# iv17-display-shield.net
KiCad netlist of a schematic drawn in EAGLE
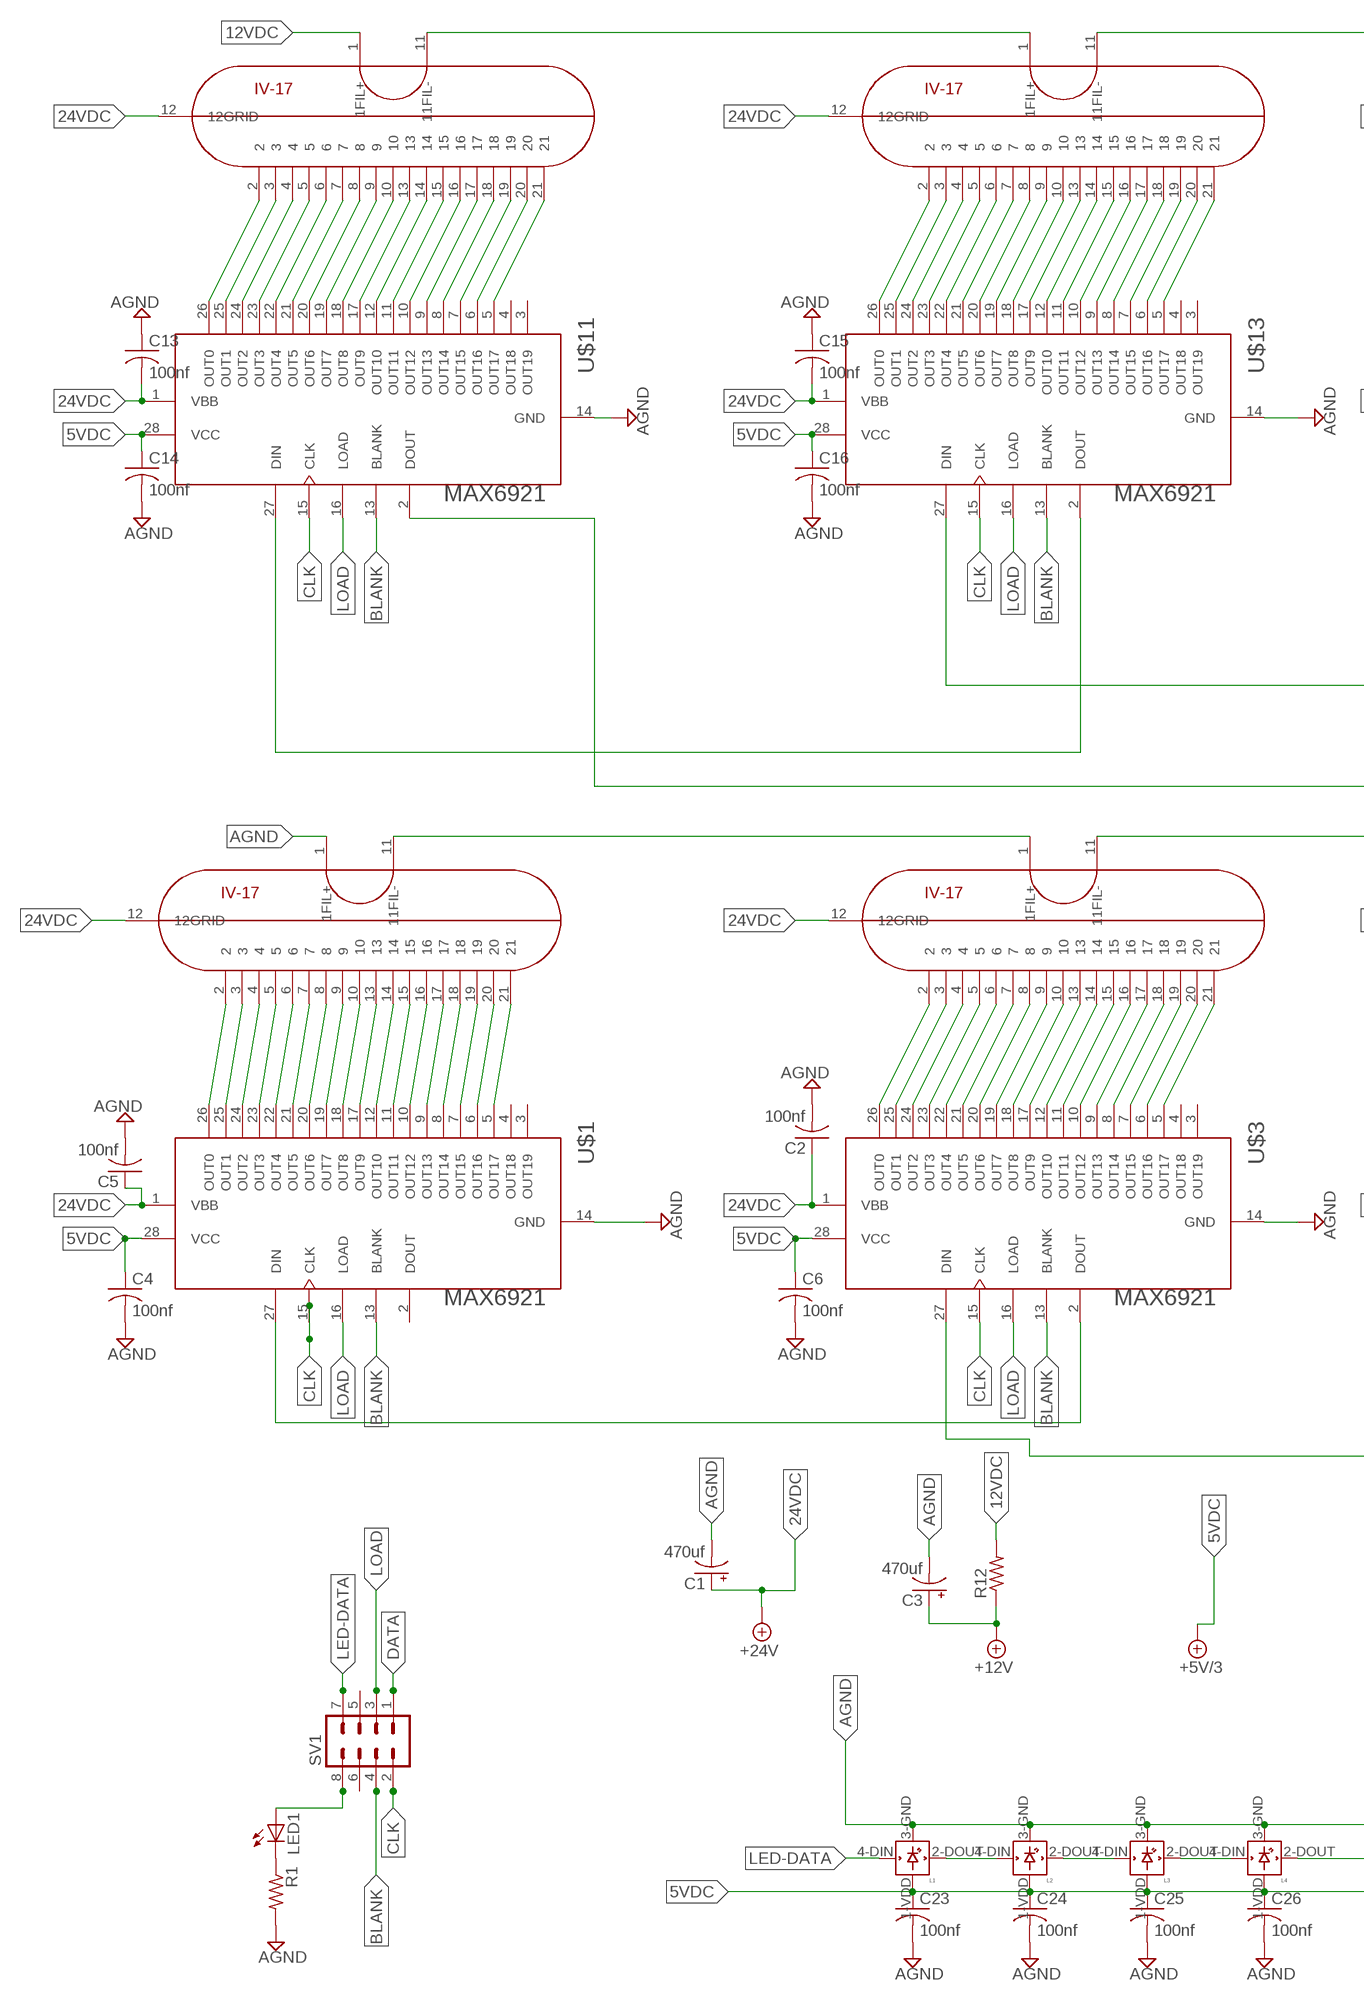
[diagram p0: schematic, sheet 1, part 1 of 2]
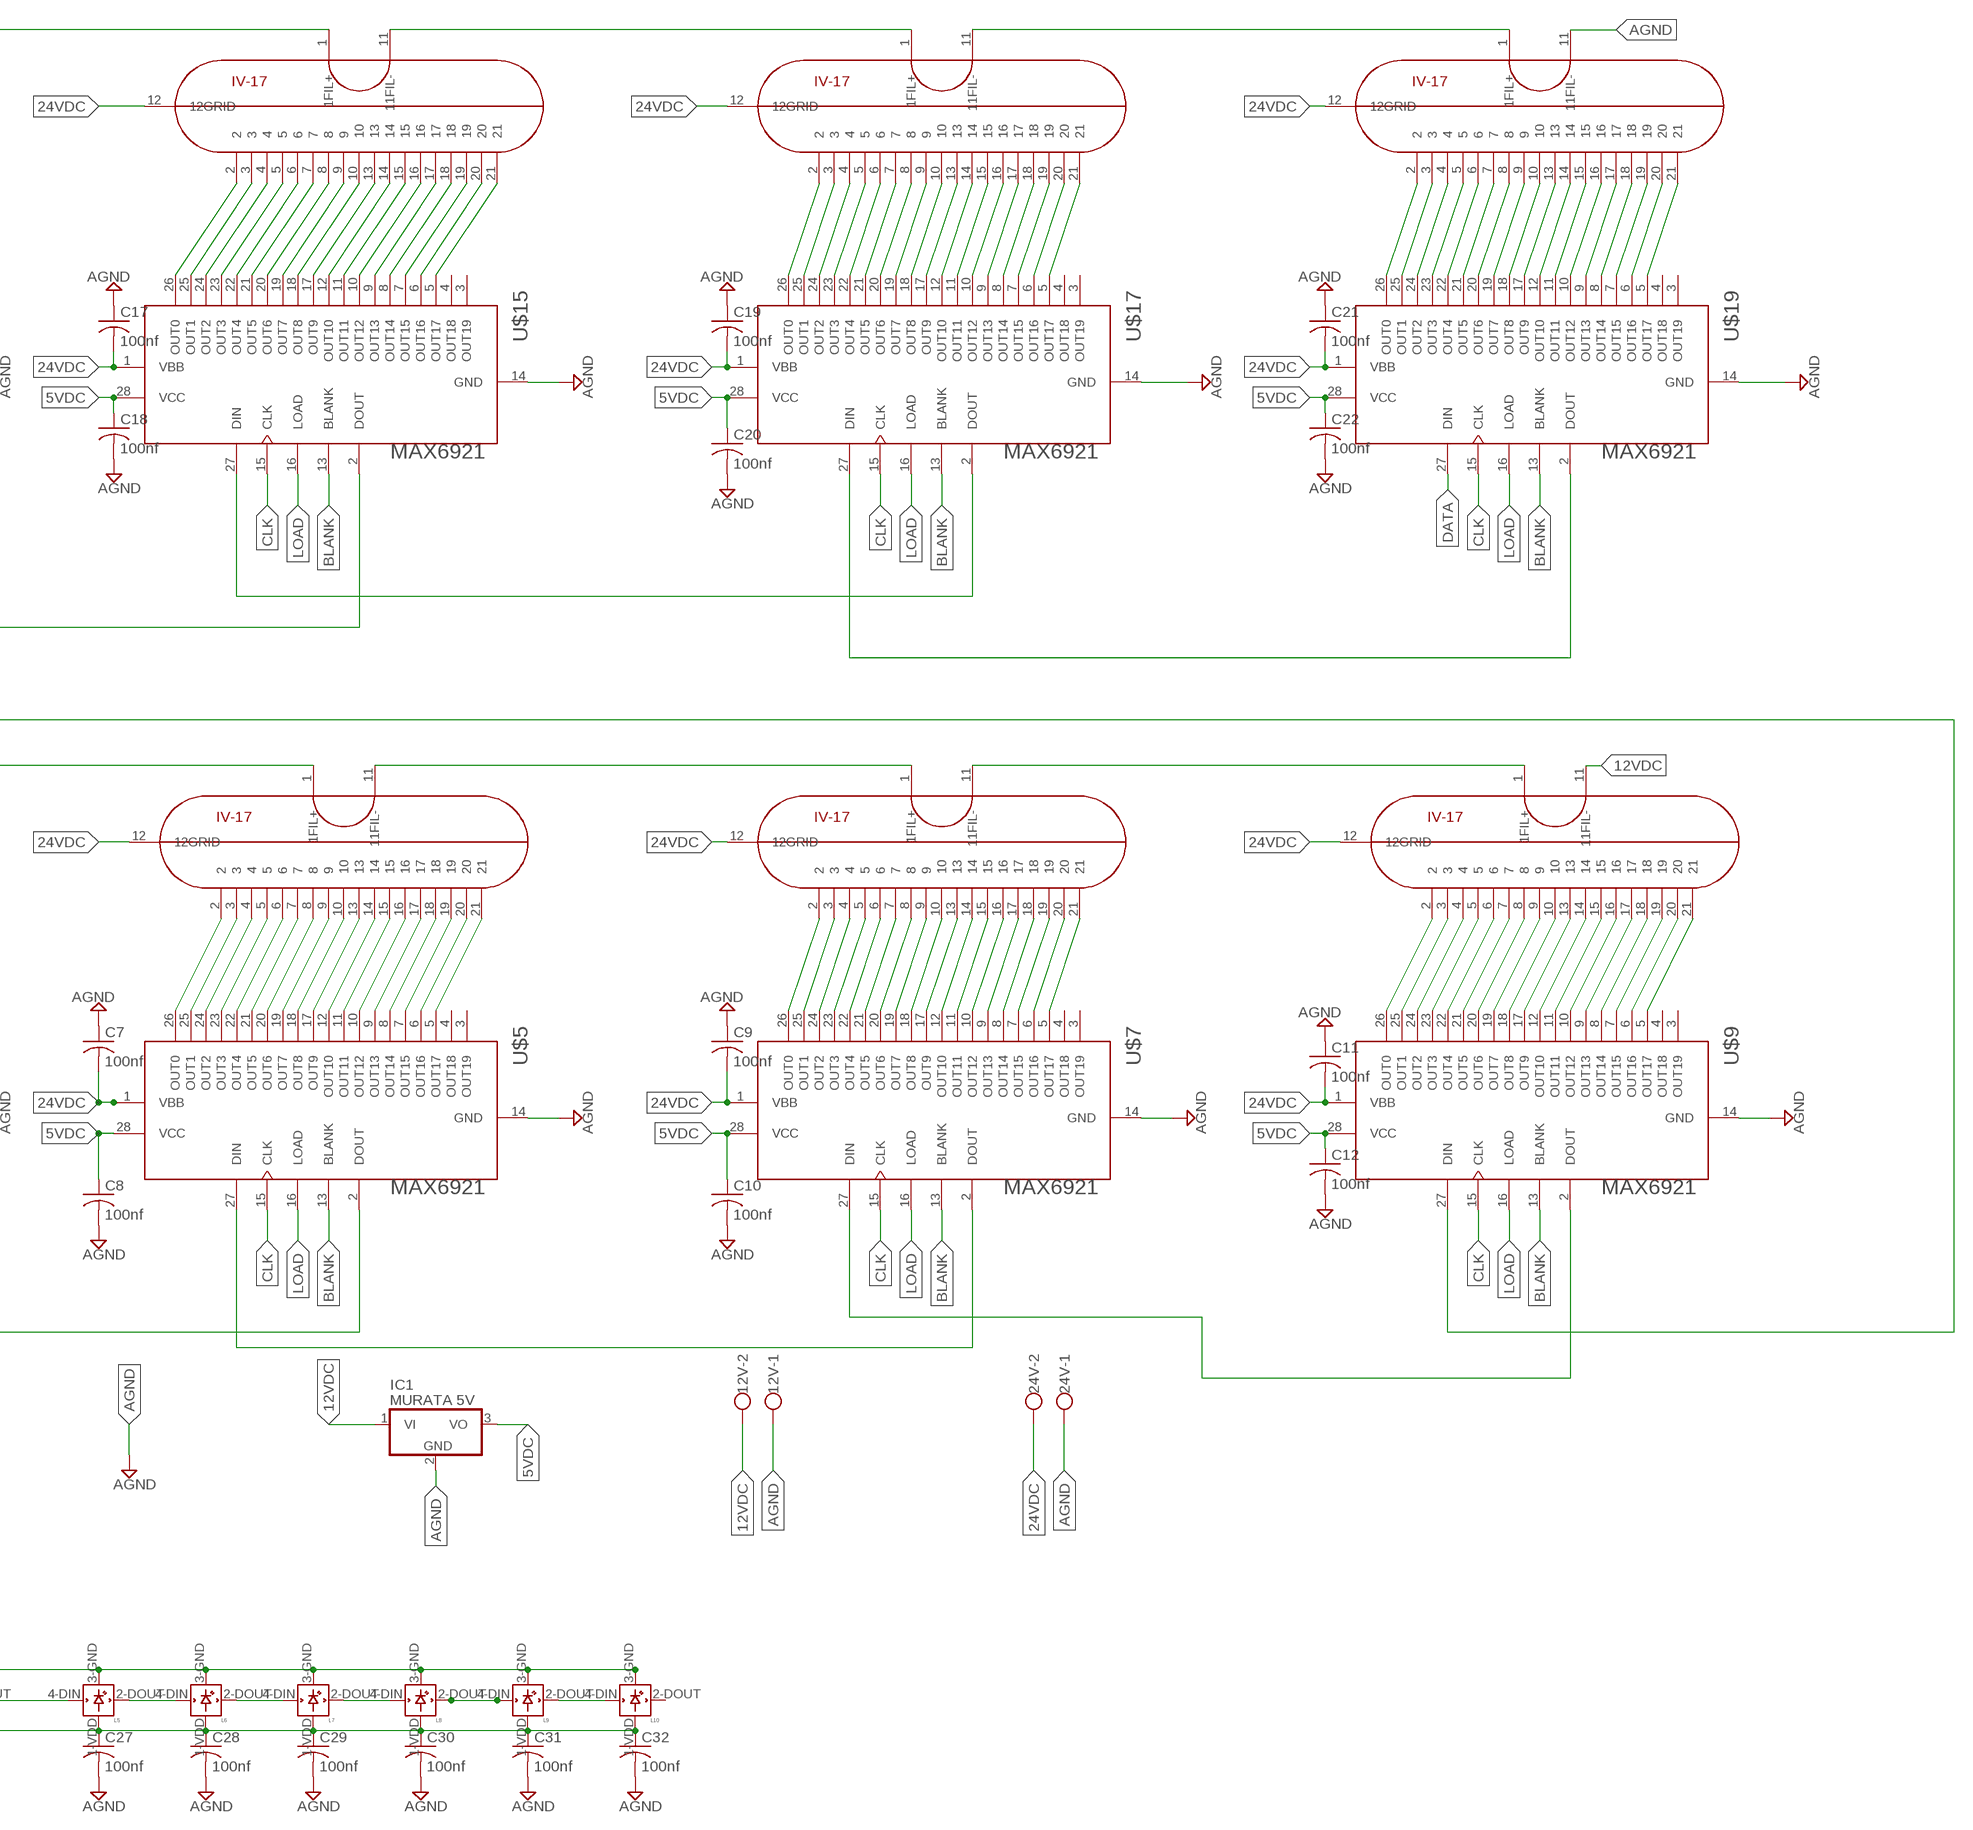
[diagram p1: schematic, sheet 1, part 2 of 2]

(export (version "E")
  (design (tool "Eeschema 10.0.6"))
  (components
    (comp (ref "12V")
      (value "W237-102")
      (footprint "eagle-import:W237-102")
      (fields (field (name "MPN") "237-102"))
      (libsource (lib "eagle-import") (part "W237-102"))
    )
    (comp (ref "24V")
      (value "W237-102")
      (footprint "eagle-import:W237-102")
      (fields (field (name "MPN") "237-102"))
      (libsource (lib "eagle-import") (part "W237-102"))
    )
    (comp (ref "C1")
      (value "470uf")
      (footprint "eagle-import:E5-10,5")
      (libsource (lib "eagle-import") (part "CPOL-USE5-10.5"))
    )
    (comp (ref "C2")
      (value "100nf")
      (footprint "eagle-import:C1206")
      (libsource (lib "eagle-import") (part "C-USC1206"))
    )
    (comp (ref "C3")
      (value "470uf")
      (footprint "eagle-import:E5-10,5")
      (libsource (lib "eagle-import") (part "CPOL-USE5-10.5"))
    )
    (comp (ref "C4")
      (value "100nf")
      (footprint "eagle-import:C1206")
      (libsource (lib "eagle-import") (part "C-USC1206"))
    )
    (comp (ref "C5")
      (value "100nf")
      (footprint "eagle-import:C1206")
      (libsource (lib "eagle-import") (part "C-USC1206"))
    )
    (comp (ref "C6")
      (value "100nf")
      (footprint "eagle-import:C1206")
      (libsource (lib "eagle-import") (part "C-USC1206"))
    )
    (comp (ref "C7")
      (value "100nf")
      (footprint "eagle-import:C1206")
      (libsource (lib "eagle-import") (part "C-USC1206"))
    )
    (comp (ref "C8")
      (value "100nf")
      (footprint "eagle-import:C1206")
      (libsource (lib "eagle-import") (part "C-USC1206"))
    )
    (comp (ref "C9")
      (value "100nf")
      (footprint "eagle-import:C1206")
      (libsource (lib "eagle-import") (part "C-USC1206"))
    )
    (comp (ref "C10")
      (value "100nf")
      (footprint "eagle-import:C1206")
      (libsource (lib "eagle-import") (part "C-USC1206"))
    )
    (comp (ref "C11")
      (value "100nf")
      (footprint "eagle-import:C1206")
      (libsource (lib "eagle-import") (part "C-USC1206"))
    )
    (comp (ref "C12")
      (value "100nf")
      (footprint "eagle-import:C1206")
      (libsource (lib "eagle-import") (part "C-USC1206"))
    )
    (comp (ref "C13")
      (value "100nf")
      (footprint "eagle-import:C1206")
      (libsource (lib "eagle-import") (part "C-USC1206"))
    )
    (comp (ref "C14")
      (value "100nf")
      (footprint "eagle-import:C1206")
      (libsource (lib "eagle-import") (part "C-USC1206"))
    )
    (comp (ref "C15")
      (value "100nf")
      (footprint "eagle-import:C1206")
      (libsource (lib "eagle-import") (part "C-USC1206"))
    )
    (comp (ref "C16")
      (value "100nf")
      (footprint "eagle-import:C1206")
      (libsource (lib "eagle-import") (part "C-USC1206"))
    )
    (comp (ref "C17")
      (value "100nf")
      (footprint "eagle-import:C1206")
      (libsource (lib "eagle-import") (part "C-USC1206"))
    )
    (comp (ref "C18")
      (value "100nf")
      (footprint "eagle-import:C1206")
      (libsource (lib "eagle-import") (part "C-USC1206"))
    )
    (comp (ref "C19")
      (value "100nf")
      (footprint "eagle-import:C1206")
      (libsource (lib "eagle-import") (part "C-USC1206"))
    )
    (comp (ref "C20")
      (value "100nf")
      (footprint "eagle-import:C1206")
      (libsource (lib "eagle-import") (part "C-USC1206"))
    )
    (comp (ref "C21")
      (value "100nf")
      (footprint "eagle-import:C1206")
      (libsource (lib "eagle-import") (part "C-USC1206"))
    )
    (comp (ref "C22")
      (value "100nf")
      (footprint "eagle-import:C1206")
      (libsource (lib "eagle-import") (part "C-USC1206"))
    )
    (comp (ref "C23")
      (value "100nf")
      (footprint "eagle-import:C1206")
      (libsource (lib "eagle-import") (part "C-USC1206"))
    )
    (comp (ref "C24")
      (value "100nf")
      (footprint "eagle-import:C1206")
      (libsource (lib "eagle-import") (part "C-USC1206"))
    )
    (comp (ref "C25")
      (value "100nf")
      (footprint "eagle-import:C1206")
      (libsource (lib "eagle-import") (part "C-USC1206"))
    )
    (comp (ref "C26")
      (value "100nf")
      (footprint "eagle-import:C1206")
      (libsource (lib "eagle-import") (part "C-USC1206"))
    )
    (comp (ref "C27")
      (value "100nf")
      (footprint "eagle-import:C1206")
      (libsource (lib "eagle-import") (part "C-USC1206"))
    )
    (comp (ref "C28")
      (value "100nf")
      (footprint "eagle-import:C1206")
      (libsource (lib "eagle-import") (part "C-USC1206"))
    )
    (comp (ref "C29")
      (value "100nf")
      (footprint "eagle-import:C1206")
      (libsource (lib "eagle-import") (part "C-USC1206"))
    )
    (comp (ref "C30")
      (value "100nf")
      (footprint "eagle-import:C1206")
      (libsource (lib "eagle-import") (part "C-USC1206"))
    )
    (comp (ref "C31")
      (value "100nf")
      (footprint "eagle-import:C1206")
      (libsource (lib "eagle-import") (part "C-USC1206"))
    )
    (comp (ref "C32")
      (value "100nf")
      (footprint "eagle-import:C1206")
      (libsource (lib "eagle-import") (part "C-USC1206"))
    )
    (comp (ref "IC1")
      (value "MURATA 5V")
      (footprint "eagle-import:TO220V")
      (libsource (lib "eagle-import") (part "78TV6"))
    )
    (comp (ref "L1")
      (value "WS2812B")
      (footprint "eagle-import:WS2812B")
      (libsource (lib "eagle-import") (part "WS2812B"))
    )
    (comp (ref "L2")
      (value "WS2812B")
      (footprint "eagle-import:WS2812B")
      (libsource (lib "eagle-import") (part "WS2812B"))
    )
    (comp (ref "L3")
      (value "WS2812B")
      (footprint "eagle-import:WS2812B")
      (libsource (lib "eagle-import") (part "WS2812B"))
    )
    (comp (ref "L4")
      (value "WS2812B")
      (footprint "eagle-import:WS2812B")
      (libsource (lib "eagle-import") (part "WS2812B"))
    )
    (comp (ref "L5")
      (value "WS2812B")
      (footprint "eagle-import:WS2812B")
      (libsource (lib "eagle-import") (part "WS2812B"))
    )
    (comp (ref "L6")
      (value "WS2812B")
      (footprint "eagle-import:WS2812B")
      (libsource (lib "eagle-import") (part "WS2812B"))
    )
    (comp (ref "L7")
      (value "WS2812B")
      (footprint "eagle-import:WS2812B")
      (libsource (lib "eagle-import") (part "WS2812B"))
    )
    (comp (ref "L8")
      (value "WS2812B")
      (footprint "eagle-import:WS2812B")
      (libsource (lib "eagle-import") (part "WS2812B"))
    )
    (comp (ref "L9")
      (value "WS2812B")
      (footprint "eagle-import:WS2812B")
      (libsource (lib "eagle-import") (part "WS2812B"))
    )
    (comp (ref "L10")
      (value "WS2812B")
      (footprint "eagle-import:WS2812B")
      (libsource (lib "eagle-import") (part "WS2812B"))
    )
    (comp (ref "LED1")
      (value "LEDSMT1206")
      (footprint "eagle-import:1206")
      (libsource (lib "eagle-import") (part "LEDSMT1206"))
    )
    (comp (ref "R1")
      (value "R-US_R1206")
      (footprint "eagle-import:R1206")
      (libsource (lib "eagle-import") (part "R-US_R1206"))
    )
    (comp (ref "R12")
      (value "R-US_0207/10")
      (footprint "eagle-import:0207_10")
      (libsource (lib "eagle-import") (part "R-US_0207/10"))
    )
    (comp (ref "SV1")
      (value "MA04-2")
      (footprint "eagle-import:MA04-2")
      (libsource (lib "eagle-import") (part "MA04-2"))
    )
    (comp (ref "U$1")
      (value "MAX6921")
      (footprint "eagle-import:SOIC-28W")
      (libsource (lib "eagle-import") (part "MAX6921"))
    )
    (comp (ref "U$2")
      (value "IV17")
      (footprint "eagle-import:NIXIE-22")
      (libsource (lib "eagle-import") (part "IV17"))
    )
    (comp (ref "U$3")
      (value "MAX6921")
      (footprint "eagle-import:SOIC-28W")
      (libsource (lib "eagle-import") (part "MAX6921"))
    )
    (comp (ref "U$4")
      (value "IV17")
      (footprint "eagle-import:NIXIE-22")
      (libsource (lib "eagle-import") (part "IV17"))
    )
    (comp (ref "U$5")
      (value "MAX6921")
      (footprint "eagle-import:SOIC-28W")
      (libsource (lib "eagle-import") (part "MAX6921"))
    )
    (comp (ref "U$6")
      (value "IV17")
      (footprint "eagle-import:NIXIE-22")
      (libsource (lib "eagle-import") (part "IV17"))
    )
    (comp (ref "U$7")
      (value "MAX6921")
      (footprint "eagle-import:SOIC-28W")
      (libsource (lib "eagle-import") (part "MAX6921"))
    )
    (comp (ref "U$8")
      (value "IV17")
      (footprint "eagle-import:NIXIE-22")
      (libsource (lib "eagle-import") (part "IV17"))
    )
    (comp (ref "U$9")
      (value "MAX6921")
      (footprint "eagle-import:SOIC-28W")
      (libsource (lib "eagle-import") (part "MAX6921"))
    )
    (comp (ref "U$10")
      (value "IV17")
      (footprint "eagle-import:NIXIE-22")
      (libsource (lib "eagle-import") (part "IV17"))
    )
    (comp (ref "U$11")
      (value "MAX6921")
      (footprint "eagle-import:SOIC-28W")
      (libsource (lib "eagle-import") (part "MAX6921"))
    )
    (comp (ref "U$12")
      (value "IV17")
      (footprint "eagle-import:NIXIE-22")
      (libsource (lib "eagle-import") (part "IV17"))
    )
    (comp (ref "U$13")
      (value "MAX6921")
      (footprint "eagle-import:SOIC-28W")
      (libsource (lib "eagle-import") (part "MAX6921"))
    )
    (comp (ref "U$14")
      (value "IV17")
      (footprint "eagle-import:NIXIE-22")
      (libsource (lib "eagle-import") (part "IV17"))
    )
    (comp (ref "U$15")
      (value "MAX6921")
      (footprint "eagle-import:SOIC-28W")
      (libsource (lib "eagle-import") (part "MAX6921"))
    )
    (comp (ref "U$16")
      (value "IV17")
      (footprint "eagle-import:NIXIE-22")
      (libsource (lib "eagle-import") (part "IV17"))
    )
    (comp (ref "U$17")
      (value "MAX6921")
      (footprint "eagle-import:SOIC-28W")
      (libsource (lib "eagle-import") (part "MAX6921"))
    )
    (comp (ref "U$18")
      (value "IV17")
      (footprint "eagle-import:NIXIE-22")
      (libsource (lib "eagle-import") (part "IV17"))
    )
    (comp (ref "U$19")
      (value "MAX6921")
      (footprint "eagle-import:SOIC-28W")
      (libsource (lib "eagle-import") (part "MAX6921"))
    )
    (comp (ref "U$20")
      (value "IV17")
      (footprint "eagle-import:NIXIE-22")
      (libsource (lib "eagle-import") (part "IV17"))
    )
  )
  (nets
    (net (code "1") (name "+12V") (class "Default")
      (node (ref "C3") (pin "+") (pinfunction "+_+") (pintype "passive"))
      (node (ref "R12") (pin "1") (pinfunction "1_1") (pintype "passive"))
    )
    (net (code "2") (name "5VDC") (class "Default")
      (node (ref "C10") (pin "1") (pinfunction "1_1") (pintype "passive"))
      (node (ref "C12") (pin "1") (pinfunction "1_1") (pintype "passive"))
      (node (ref "C14") (pin "1") (pinfunction "1_1") (pintype "passive"))
      (node (ref "C16") (pin "1") (pinfunction "1_1") (pintype "passive"))
      (node (ref "C18") (pin "1") (pinfunction "1_1") (pintype "passive"))
      (node (ref "C20") (pin "1") (pinfunction "1_1") (pintype "passive"))
      (node (ref "C22") (pin "1") (pinfunction "1_1") (pintype "passive"))
      (node (ref "C23") (pin "1") (pinfunction "1_1") (pintype "passive"))
      (node (ref "C24") (pin "1") (pinfunction "1_1") (pintype "passive"))
      (node (ref "C25") (pin "1") (pinfunction "1_1") (pintype "passive"))
      (node (ref "C26") (pin "1") (pinfunction "1_1") (pintype "passive"))
      (node (ref "C27") (pin "1") (pinfunction "1_1") (pintype "passive"))
      (node (ref "C28") (pin "1") (pinfunction "1_1") (pintype "passive"))
      (node (ref "C29") (pin "1") (pinfunction "1_1") (pintype "passive"))
      (node (ref "C30") (pin "1") (pinfunction "1_1") (pintype "passive"))
      (node (ref "C31") (pin "1") (pinfunction "1_1") (pintype "passive"))
      (node (ref "C32") (pin "1") (pinfunction "1_1") (pintype "passive"))
      (node (ref "C4") (pin "1") (pinfunction "1_1") (pintype "passive"))
      (node (ref "C6") (pin "1") (pinfunction "1_1") (pintype "passive"))
      (node (ref "C8") (pin "1") (pinfunction "1_1") (pintype "passive"))
      (node (ref "IC1") (pin "3") (pinfunction "VO_3") (pintype "passive"))
      (node (ref "L1") (pin "1-VDD") (pinfunction "VDD_1-VDD") (pintype "bidirectional"))
      (node (ref "L10") (pin "1-VDD") (pinfunction "VDD_1-VDD") (pintype "bidirectional"))
      (node (ref "L2") (pin "1-VDD") (pinfunction "VDD_1-VDD") (pintype "bidirectional"))
      (node (ref "L3") (pin "1-VDD") (pinfunction "VDD_1-VDD") (pintype "bidirectional"))
      (node (ref "L4") (pin "1-VDD") (pinfunction "VDD_1-VDD") (pintype "bidirectional"))
      (node (ref "L5") (pin "1-VDD") (pinfunction "VDD_1-VDD") (pintype "bidirectional"))
      (node (ref "L6") (pin "1-VDD") (pinfunction "VDD_1-VDD") (pintype "bidirectional"))
      (node (ref "L7") (pin "1-VDD") (pinfunction "VDD_1-VDD") (pintype "bidirectional"))
      (node (ref "L8") (pin "1-VDD") (pinfunction "VDD_1-VDD") (pintype "bidirectional"))
      (node (ref "L9") (pin "1-VDD") (pinfunction "VDD_1-VDD") (pintype "bidirectional"))
      (node (ref "U$1") (pin "28") (pinfunction "VCC_28") (pintype "power_in"))
      (node (ref "U$11") (pin "28") (pinfunction "VCC_28") (pintype "power_in"))
      (node (ref "U$13") (pin "28") (pinfunction "VCC_28") (pintype "power_in"))
      (node (ref "U$15") (pin "28") (pinfunction "VCC_28") (pintype "power_in"))
      (node (ref "U$17") (pin "28") (pinfunction "VCC_28") (pintype "power_in"))
      (node (ref "U$19") (pin "28") (pinfunction "VCC_28") (pintype "power_in"))
      (node (ref "U$3") (pin "28") (pinfunction "VCC_28") (pintype "power_in"))
      (node (ref "U$5") (pin "28") (pinfunction "VCC_28") (pintype "power_in"))
      (node (ref "U$7") (pin "28") (pinfunction "VCC_28") (pintype "power_in"))
      (node (ref "U$9") (pin "28") (pinfunction "VCC_28") (pintype "power_in"))
    )
    (net (code "3") (name "12VDC") (class "Default")
      (node (ref "12V") (pin "2") (pinfunction "KL_2") (pintype "passive"))
      (node (ref "IC1") (pin "1") (pinfunction "VI_1") (pintype "input"))
      (node (ref "R12") (pin "2") (pinfunction "2_2") (pintype "passive"))
      (node (ref "U$10") (pin "11") (pinfunction "11FIL-_11") (pintype "bidirectional"))
      (node (ref "U$12") (pin "1") (pinfunction "1FIL+_1") (pintype "bidirectional"))
    )
    (net (code "4") (name "24VDC") (class "Default")
      (node (ref "24V") (pin "2") (pinfunction "KL_2") (pintype "passive"))
      (node (ref "C1") (pin "+") (pinfunction "+_+") (pintype "passive"))
      (node (ref "C11") (pin "2") (pinfunction "2_2") (pintype "passive"))
      (node (ref "C13") (pin "2") (pinfunction "2_2") (pintype "passive"))
      (node (ref "C15") (pin "2") (pinfunction "2_2") (pintype "passive"))
      (node (ref "C17") (pin "2") (pinfunction "2_2") (pintype "passive"))
      (node (ref "C19") (pin "2") (pinfunction "2_2") (pintype "passive"))
      (node (ref "C2") (pin "1") (pinfunction "1_1") (pintype "passive"))
      (node (ref "C21") (pin "2") (pinfunction "2_2") (pintype "passive"))
      (node (ref "C5") (pin "1") (pinfunction "1_1") (pintype "passive"))
      (node (ref "C7") (pin "2") (pinfunction "2_2") (pintype "passive"))
      (node (ref "C9") (pin "2") (pinfunction "2_2") (pintype "passive"))
      (node (ref "U$1") (pin "1") (pinfunction "VBB_1") (pintype "power_in"))
      (node (ref "U$10") (pin "12") (pinfunction "12GRID_12") (pintype "bidirectional"))
      (node (ref "U$11") (pin "1") (pinfunction "VBB_1") (pintype "power_in"))
      (node (ref "U$12") (pin "12") (pinfunction "12GRID_12") (pintype "bidirectional"))
      (node (ref "U$13") (pin "1") (pinfunction "VBB_1") (pintype "power_in"))
      (node (ref "U$14") (pin "12") (pinfunction "12GRID_12") (pintype "bidirectional"))
      (node (ref "U$15") (pin "1") (pinfunction "VBB_1") (pintype "power_in"))
      (node (ref "U$16") (pin "12") (pinfunction "12GRID_12") (pintype "bidirectional"))
      (node (ref "U$17") (pin "1") (pinfunction "VBB_1") (pintype "power_in"))
      (node (ref "U$18") (pin "12") (pinfunction "12GRID_12") (pintype "bidirectional"))
      (node (ref "U$19") (pin "1") (pinfunction "VBB_1") (pintype "power_in"))
      (node (ref "U$2") (pin "12") (pinfunction "12GRID_12") (pintype "bidirectional"))
      (node (ref "U$20") (pin "12") (pinfunction "12GRID_12") (pintype "bidirectional"))
      (node (ref "U$3") (pin "1") (pinfunction "VBB_1") (pintype "power_in"))
      (node (ref "U$4") (pin "12") (pinfunction "12GRID_12") (pintype "bidirectional"))
      (node (ref "U$5") (pin "1") (pinfunction "VBB_1") (pintype "power_in"))
      (node (ref "U$6") (pin "12") (pinfunction "12GRID_12") (pintype "bidirectional"))
      (node (ref "U$7") (pin "1") (pinfunction "VBB_1") (pintype "power_in"))
      (node (ref "U$8") (pin "12") (pinfunction "12GRID_12") (pintype "bidirectional"))
      (node (ref "U$9") (pin "1") (pinfunction "VBB_1") (pintype "power_in"))
    )
    (net (code "5") (name "AGND") (class "Default")
      (node (ref "12V") (pin "1") (pinfunction "KL_1") (pintype "passive"))
      (node (ref "24V") (pin "1") (pinfunction "KL_1") (pintype "passive"))
      (node (ref "C1") (pin "-") (pinfunction "-_-") (pintype "passive"))
      (node (ref "C10") (pin "2") (pinfunction "2_2") (pintype "passive"))
      (node (ref "C11") (pin "1") (pinfunction "1_1") (pintype "passive"))
      (node (ref "C12") (pin "2") (pinfunction "2_2") (pintype "passive"))
      (node (ref "C13") (pin "1") (pinfunction "1_1") (pintype "passive"))
      (node (ref "C14") (pin "2") (pinfunction "2_2") (pintype "passive"))
      (node (ref "C15") (pin "1") (pinfunction "1_1") (pintype "passive"))
      (node (ref "C16") (pin "2") (pinfunction "2_2") (pintype "passive"))
      (node (ref "C17") (pin "1") (pinfunction "1_1") (pintype "passive"))
      (node (ref "C18") (pin "2") (pinfunction "2_2") (pintype "passive"))
      (node (ref "C19") (pin "1") (pinfunction "1_1") (pintype "passive"))
      (node (ref "C2") (pin "2") (pinfunction "2_2") (pintype "passive"))
      (node (ref "C20") (pin "2") (pinfunction "2_2") (pintype "passive"))
      (node (ref "C21") (pin "1") (pinfunction "1_1") (pintype "passive"))
      (node (ref "C22") (pin "2") (pinfunction "2_2") (pintype "passive"))
      (node (ref "C23") (pin "2") (pinfunction "2_2") (pintype "passive"))
      (node (ref "C24") (pin "2") (pinfunction "2_2") (pintype "passive"))
      (node (ref "C25") (pin "2") (pinfunction "2_2") (pintype "passive"))
      (node (ref "C26") (pin "2") (pinfunction "2_2") (pintype "passive"))
      (node (ref "C27") (pin "2") (pinfunction "2_2") (pintype "passive"))
      (node (ref "C28") (pin "2") (pinfunction "2_2") (pintype "passive"))
      (node (ref "C29") (pin "2") (pinfunction "2_2") (pintype "passive"))
      (node (ref "C3") (pin "-") (pinfunction "-_-") (pintype "passive"))
      (node (ref "C30") (pin "2") (pinfunction "2_2") (pintype "passive"))
      (node (ref "C31") (pin "2") (pinfunction "2_2") (pintype "passive"))
      (node (ref "C32") (pin "2") (pinfunction "2_2") (pintype "passive"))
      (node (ref "C4") (pin "2") (pinfunction "2_2") (pintype "passive"))
      (node (ref "C5") (pin "2") (pinfunction "2_2") (pintype "passive"))
      (node (ref "C6") (pin "2") (pinfunction "2_2") (pintype "passive"))
      (node (ref "C7") (pin "1") (pinfunction "1_1") (pintype "passive"))
      (node (ref "C8") (pin "2") (pinfunction "2_2") (pintype "passive"))
      (node (ref "C9") (pin "1") (pinfunction "1_1") (pintype "passive"))
      (node (ref "IC1") (pin "2") (pinfunction "GND_2") (pintype "passive"))
      (node (ref "L1") (pin "3-GND") (pinfunction "GND_3-GND") (pintype "bidirectional"))
      (node (ref "L10") (pin "3-GND") (pinfunction "GND_3-GND") (pintype "bidirectional"))
      (node (ref "L2") (pin "3-GND") (pinfunction "GND_3-GND") (pintype "bidirectional"))
      (node (ref "L3") (pin "3-GND") (pinfunction "GND_3-GND") (pintype "bidirectional"))
      (node (ref "L4") (pin "3-GND") (pinfunction "GND_3-GND") (pintype "bidirectional"))
      (node (ref "L5") (pin "3-GND") (pinfunction "GND_3-GND") (pintype "bidirectional"))
      (node (ref "L6") (pin "3-GND") (pinfunction "GND_3-GND") (pintype "bidirectional"))
      (node (ref "L7") (pin "3-GND") (pinfunction "GND_3-GND") (pintype "bidirectional"))
      (node (ref "L8") (pin "3-GND") (pinfunction "GND_3-GND") (pintype "bidirectional"))
      (node (ref "L9") (pin "3-GND") (pinfunction "GND_3-GND") (pintype "bidirectional"))
      (node (ref "R1") (pin "2") (pinfunction "2_2") (pintype "passive"))
      (node (ref "U$1") (pin "14") (pinfunction "GND_14") (pintype "power_in"))
      (node (ref "U$11") (pin "14") (pinfunction "GND_14") (pintype "power_in"))
      (node (ref "U$13") (pin "14") (pinfunction "GND_14") (pintype "power_in"))
      (node (ref "U$15") (pin "14") (pinfunction "GND_14") (pintype "power_in"))
      (node (ref "U$17") (pin "14") (pinfunction "GND_14") (pintype "power_in"))
      (node (ref "U$19") (pin "14") (pinfunction "GND_14") (pintype "power_in"))
      (node (ref "U$2") (pin "1") (pinfunction "1FIL+_1") (pintype "bidirectional"))
      (node (ref "U$20") (pin "11") (pinfunction "11FIL-_11") (pintype "bidirectional"))
      (node (ref "U$3") (pin "14") (pinfunction "GND_14") (pintype "power_in"))
      (node (ref "U$5") (pin "14") (pinfunction "GND_14") (pintype "power_in"))
      (node (ref "U$7") (pin "14") (pinfunction "GND_14") (pintype "power_in"))
      (node (ref "U$9") (pin "14") (pinfunction "GND_14") (pintype "power_in"))
    )
    (net (code "6") (name "BLANK") (class "Default")
      (node (ref "SV1") (pin "4") (pinfunction "4_4") (pintype "passive"))
      (node (ref "U$1") (pin "13") (pinfunction "BLANK_13") (pintype "input"))
      (node (ref "U$11") (pin "13") (pinfunction "BLANK_13") (pintype "input"))
      (node (ref "U$13") (pin "13") (pinfunction "BLANK_13") (pintype "input"))
      (node (ref "U$15") (pin "13") (pinfunction "BLANK_13") (pintype "input"))
      (node (ref "U$17") (pin "13") (pinfunction "BLANK_13") (pintype "input"))
      (node (ref "U$19") (pin "13") (pinfunction "BLANK_13") (pintype "input"))
      (node (ref "U$3") (pin "13") (pinfunction "BLANK_13") (pintype "input"))
      (node (ref "U$5") (pin "13") (pinfunction "BLANK_13") (pintype "input"))
      (node (ref "U$7") (pin "13") (pinfunction "BLANK_13") (pintype "input"))
      (node (ref "U$9") (pin "13") (pinfunction "BLANK_13") (pintype "input"))
    )
    (net (code "7") (name "CLK") (class "Default")
      (node (ref "SV1") (pin "2") (pinfunction "2_2") (pintype "passive"))
      (node (ref "U$1") (pin "15") (pinfunction "CLK_15") (pintype "input"))
      (node (ref "U$11") (pin "15") (pinfunction "CLK_15") (pintype "input"))
      (node (ref "U$13") (pin "15") (pinfunction "CLK_15") (pintype "input"))
      (node (ref "U$15") (pin "15") (pinfunction "CLK_15") (pintype "input"))
      (node (ref "U$17") (pin "15") (pinfunction "CLK_15") (pintype "input"))
      (node (ref "U$19") (pin "15") (pinfunction "CLK_15") (pintype "input"))
      (node (ref "U$3") (pin "15") (pinfunction "CLK_15") (pintype "input"))
      (node (ref "U$5") (pin "15") (pinfunction "CLK_15") (pintype "input"))
      (node (ref "U$7") (pin "15") (pinfunction "CLK_15") (pintype "input"))
      (node (ref "U$9") (pin "15") (pinfunction "CLK_15") (pintype "input"))
    )
    (net (code "8") (name "DATA") (class "Default")
      (node (ref "SV1") (pin "1") (pinfunction "1_1") (pintype "passive"))
      (node (ref "U$19") (pin "27") (pinfunction "DIN_27") (pintype "input"))
    )
    (net (code "9") (name "LED-DATA") (class "Default")
      (node (ref "L1") (pin "4-DIN") (pinfunction "DIN_4-DIN") (pintype "input"))
      (node (ref "SV1") (pin "7") (pinfunction "7_7") (pintype "passive"))
    )
    (net (code "10") (name "LOAD") (class "Default")
      (node (ref "SV1") (pin "3") (pinfunction "3_3") (pintype "passive"))
      (node (ref "U$1") (pin "16") (pinfunction "LOAD_16") (pintype "input"))
      (node (ref "U$11") (pin "16") (pinfunction "LOAD_16") (pintype "input"))
      (node (ref "U$13") (pin "16") (pinfunction "LOAD_16") (pintype "input"))
      (node (ref "U$15") (pin "16") (pinfunction "LOAD_16") (pintype "input"))
      (node (ref "U$17") (pin "16") (pinfunction "LOAD_16") (pintype "input"))
      (node (ref "U$19") (pin "16") (pinfunction "LOAD_16") (pintype "input"))
      (node (ref "U$3") (pin "16") (pinfunction "LOAD_16") (pintype "input"))
      (node (ref "U$5") (pin "16") (pinfunction "LOAD_16") (pintype "input"))
      (node (ref "U$7") (pin "16") (pinfunction "LOAD_16") (pintype "input"))
      (node (ref "U$9") (pin "16") (pinfunction "LOAD_16") (pintype "input"))
    )
    (net (code "11") (name "Net-(L1-DOUT)") (class "Default")
      (node (ref "L1") (pin "2-DOUT") (pinfunction "DOUT_2-DOUT") (pintype "output"))
      (node (ref "L2") (pin "4-DIN") (pinfunction "DIN_4-DIN") (pintype "input"))
    )
    (net (code "12") (name "Net-(L2-DOUT)") (class "Default")
      (node (ref "L2") (pin "2-DOUT") (pinfunction "DOUT_2-DOUT") (pintype "output"))
      (node (ref "L3") (pin "4-DIN") (pinfunction "DIN_4-DIN") (pintype "input"))
    )
    (net (code "13") (name "Net-(L3-DOUT)") (class "Default")
      (node (ref "L3") (pin "2-DOUT") (pinfunction "DOUT_2-DOUT") (pintype "output"))
      (node (ref "L4") (pin "4-DIN") (pinfunction "DIN_4-DIN") (pintype "input"))
    )
    (net (code "14") (name "Net-(L4-DOUT)") (class "Default")
      (node (ref "L4") (pin "2-DOUT") (pinfunction "DOUT_2-DOUT") (pintype "output"))
      (node (ref "L5") (pin "4-DIN") (pinfunction "DIN_4-DIN") (pintype "input"))
    )
    (net (code "15") (name "Net-(L5-DOUT)") (class "Default")
      (node (ref "L5") (pin "2-DOUT") (pinfunction "DOUT_2-DOUT") (pintype "output"))
      (node (ref "L6") (pin "4-DIN") (pinfunction "DIN_4-DIN") (pintype "input"))
    )
    (net (code "16") (name "Net-(L6-DOUT)") (class "Default")
      (node (ref "L6") (pin "2-DOUT") (pinfunction "DOUT_2-DOUT") (pintype "output"))
      (node (ref "L7") (pin "4-DIN") (pinfunction "DIN_4-DIN") (pintype "input"))
    )
    (net (code "17") (name "Net-(L7-DOUT)") (class "Default")
      (node (ref "L7") (pin "2-DOUT") (pinfunction "DOUT_2-DOUT") (pintype "output"))
      (node (ref "L8") (pin "4-DIN") (pinfunction "DIN_4-DIN") (pintype "input"))
    )
    (net (code "18") (name "Net-(L8-DOUT)") (class "Default")
      (node (ref "L8") (pin "2-DOUT") (pinfunction "DOUT_2-DOUT") (pintype "output"))
      (node (ref "L9") (pin "4-DIN") (pinfunction "DIN_4-DIN") (pintype "input"))
    )
    (net (code "19") (name "Net-(L10-DIN)") (class "Default")
      (node (ref "L10") (pin "4-DIN") (pinfunction "DIN_4-DIN") (pintype "input"))
      (node (ref "L9") (pin "2-DOUT") (pinfunction "DOUT_2-DOUT") (pintype "output"))
    )
    (net (code "20") (name "Net-(LED1-PadA)") (class "Default")
      (node (ref "LED1") (pin "A") (pinfunction "A_A") (pintype "passive"))
      (node (ref "SV1") (pin "8") (pinfunction "8_8") (pintype "passive"))
    )
    (net (code "21") (name "Net-(LED1-PadC)") (class "Default")
      (node (ref "LED1") (pin "C") (pinfunction "C_C") (pintype "passive"))
      (node (ref "R1") (pin "1") (pinfunction "1_1") (pintype "passive"))
    )
    (net (code "22") (name "Net-(U$1-DIN)") (class "Default")
      (node (ref "U$1") (pin "27") (pinfunction "DIN_27") (pintype "input"))
      (node (ref "U$3") (pin "2") (pinfunction "DOUT_2") (pintype "output"))
    )
    (net (code "23") (name "Net-(U$1-OUT0)") (class "Default")
      (node (ref "U$1") (pin "26") (pinfunction "OUT0_26") (pintype "output"))
      (node (ref "U$2") (pin "2") (pinfunction "2_2") (pintype "bidirectional"))
    )
    (net (code "24") (name "Net-(U$1-OUT1)") (class "Default")
      (node (ref "U$1") (pin "25") (pinfunction "OUT1_25") (pintype "output"))
      (node (ref "U$2") (pin "3") (pinfunction "3_3") (pintype "bidirectional"))
    )
    (net (code "25") (name "Net-(U$1-OUT2)") (class "Default")
      (node (ref "U$1") (pin "24") (pinfunction "OUT2_24") (pintype "output"))
      (node (ref "U$2") (pin "4") (pinfunction "4_4") (pintype "bidirectional"))
    )
    (net (code "26") (name "Net-(U$1-OUT3)") (class "Default")
      (node (ref "U$1") (pin "23") (pinfunction "OUT3_23") (pintype "output"))
      (node (ref "U$2") (pin "5") (pinfunction "5_5") (pintype "bidirectional"))
    )
    (net (code "27") (name "Net-(U$1-OUT4)") (class "Default")
      (node (ref "U$1") (pin "22") (pinfunction "OUT4_22") (pintype "output"))
      (node (ref "U$2") (pin "6") (pinfunction "6_6") (pintype "bidirectional"))
    )
    (net (code "28") (name "Net-(U$1-OUT5)") (class "Default")
      (node (ref "U$1") (pin "21") (pinfunction "OUT5_21") (pintype "output"))
      (node (ref "U$2") (pin "7") (pinfunction "7_7") (pintype "bidirectional"))
    )
    (net (code "29") (name "Net-(U$1-OUT6)") (class "Default")
      (node (ref "U$1") (pin "20") (pinfunction "OUT6_20") (pintype "output"))
      (node (ref "U$2") (pin "8") (pinfunction "8_8") (pintype "bidirectional"))
    )
    (net (code "30") (name "Net-(U$1-OUT7)") (class "Default")
      (node (ref "U$1") (pin "19") (pinfunction "OUT7_19") (pintype "output"))
      (node (ref "U$2") (pin "9") (pinfunction "9_9") (pintype "bidirectional"))
    )
    (net (code "31") (name "Net-(U$1-OUT8)") (class "Default")
      (node (ref "U$1") (pin "18") (pinfunction "OUT8_18") (pintype "output"))
      (node (ref "U$2") (pin "10") (pinfunction "10_10") (pintype "bidirectional"))
    )
    (net (code "32") (name "Net-(U$1-OUT9)") (class "Default")
      (node (ref "U$1") (pin "17") (pinfunction "OUT9_17") (pintype "output"))
      (node (ref "U$2") (pin "13") (pinfunction "13_13") (pintype "bidirectional"))
    )
    (net (code "33") (name "Net-(U$1-OUT10)") (class "Default")
      (node (ref "U$1") (pin "12") (pinfunction "OUT10_12") (pintype "output"))
      (node (ref "U$2") (pin "14") (pinfunction "14_14") (pintype "bidirectional"))
    )
    (net (code "34") (name "Net-(U$1-OUT11)") (class "Default")
      (node (ref "U$1") (pin "11") (pinfunction "OUT11_11") (pintype "output"))
      (node (ref "U$2") (pin "15") (pinfunction "15_15") (pintype "bidirectional"))
    )
    (net (code "35") (name "Net-(U$1-OUT12)") (class "Default")
      (node (ref "U$1") (pin "10") (pinfunction "OUT12_10") (pintype "output"))
      (node (ref "U$2") (pin "16") (pinfunction "16_16") (pintype "bidirectional"))
    )
    (net (code "36") (name "Net-(U$1-OUT13)") (class "Default")
      (node (ref "U$1") (pin "9") (pinfunction "OUT13_9") (pintype "output"))
      (node (ref "U$2") (pin "17") (pinfunction "17_17") (pintype "bidirectional"))
    )
    (net (code "37") (name "Net-(U$1-OUT14)") (class "Default")
      (node (ref "U$1") (pin "8") (pinfunction "OUT14_8") (pintype "output"))
      (node (ref "U$2") (pin "18") (pinfunction "18_18") (pintype "bidirectional"))
    )
    (net (code "38") (name "Net-(U$1-OUT15)") (class "Default")
      (node (ref "U$1") (pin "7") (pinfunction "OUT15_7") (pintype "output"))
      (node (ref "U$2") (pin "19") (pinfunction "19_19") (pintype "bidirectional"))
    )
    (net (code "39") (name "Net-(U$1-OUT16)") (class "Default")
      (node (ref "U$1") (pin "6") (pinfunction "OUT16_6") (pintype "output"))
      (node (ref "U$2") (pin "20") (pinfunction "20_20") (pintype "bidirectional"))
    )
    (net (code "40") (name "Net-(U$1-OUT17)") (class "Default")
      (node (ref "U$1") (pin "5") (pinfunction "OUT17_5") (pintype "output"))
      (node (ref "U$2") (pin "21") (pinfunction "21_21") (pintype "bidirectional"))
    )
    (net (code "41") (name "Net-(U$2-11FIL-)") (class "Default")
      (node (ref "U$2") (pin "11") (pinfunction "11FIL-_11") (pintype "bidirectional"))
      (node (ref "U$4") (pin "1") (pinfunction "1FIL+_1") (pintype "bidirectional"))
    )
    (net (code "42") (name "Net-(U$3-DIN)") (class "Default")
      (node (ref "U$3") (pin "27") (pinfunction "DIN_27") (pintype "input"))
      (node (ref "U$5") (pin "2") (pinfunction "DOUT_2") (pintype "output"))
    )
    (net (code "43") (name "Net-(U$3-OUT0)") (class "Default")
      (node (ref "U$3") (pin "26") (pinfunction "OUT0_26") (pintype "output"))
      (node (ref "U$4") (pin "2") (pinfunction "2_2") (pintype "bidirectional"))
    )
    (net (code "44") (name "Net-(U$3-OUT1)") (class "Default")
      (node (ref "U$3") (pin "25") (pinfunction "OUT1_25") (pintype "output"))
      (node (ref "U$4") (pin "3") (pinfunction "3_3") (pintype "bidirectional"))
    )
    (net (code "45") (name "Net-(U$3-OUT2)") (class "Default")
      (node (ref "U$3") (pin "24") (pinfunction "OUT2_24") (pintype "output"))
      (node (ref "U$4") (pin "4") (pinfunction "4_4") (pintype "bidirectional"))
    )
    (net (code "46") (name "Net-(U$3-OUT3)") (class "Default")
      (node (ref "U$3") (pin "23") (pinfunction "OUT3_23") (pintype "output"))
      (node (ref "U$4") (pin "5") (pinfunction "5_5") (pintype "bidirectional"))
    )
    (net (code "47") (name "Net-(U$3-OUT4)") (class "Default")
      (node (ref "U$3") (pin "22") (pinfunction "OUT4_22") (pintype "output"))
      (node (ref "U$4") (pin "6") (pinfunction "6_6") (pintype "bidirectional"))
    )
    (net (code "48") (name "Net-(U$3-OUT5)") (class "Default")
      (node (ref "U$3") (pin "21") (pinfunction "OUT5_21") (pintype "output"))
      (node (ref "U$4") (pin "7") (pinfunction "7_7") (pintype "bidirectional"))
    )
    (net (code "49") (name "Net-(U$3-OUT6)") (class "Default")
      (node (ref "U$3") (pin "20") (pinfunction "OUT6_20") (pintype "output"))
      (node (ref "U$4") (pin "8") (pinfunction "8_8") (pintype "bidirectional"))
    )
    (net (code "50") (name "Net-(U$3-OUT7)") (class "Default")
      (node (ref "U$3") (pin "19") (pinfunction "OUT7_19") (pintype "output"))
      (node (ref "U$4") (pin "9") (pinfunction "9_9") (pintype "bidirectional"))
    )
    (net (code "51") (name "Net-(U$3-OUT8)") (class "Default")
      (node (ref "U$3") (pin "18") (pinfunction "OUT8_18") (pintype "output"))
      (node (ref "U$4") (pin "10") (pinfunction "10_10") (pintype "bidirectional"))
    )
    (net (code "52") (name "Net-(U$3-OUT9)") (class "Default")
      (node (ref "U$3") (pin "17") (pinfunction "OUT9_17") (pintype "output"))
      (node (ref "U$4") (pin "13") (pinfunction "13_13") (pintype "bidirectional"))
    )
    (net (code "53") (name "Net-(U$3-OUT10)") (class "Default")
      (node (ref "U$3") (pin "12") (pinfunction "OUT10_12") (pintype "output"))
      (node (ref "U$4") (pin "14") (pinfunction "14_14") (pintype "bidirectional"))
    )
    (net (code "54") (name "Net-(U$3-OUT11)") (class "Default")
      (node (ref "U$3") (pin "11") (pinfunction "OUT11_11") (pintype "output"))
      (node (ref "U$4") (pin "15") (pinfunction "15_15") (pintype "bidirectional"))
    )
    (net (code "55") (name "Net-(U$3-OUT12)") (class "Default")
      (node (ref "U$3") (pin "10") (pinfunction "OUT12_10") (pintype "output"))
      (node (ref "U$4") (pin "16") (pinfunction "16_16") (pintype "bidirectional"))
    )
    (net (code "56") (name "Net-(U$3-OUT13)") (class "Default")
      (node (ref "U$3") (pin "9") (pinfunction "OUT13_9") (pintype "output"))
      (node (ref "U$4") (pin "17") (pinfunction "17_17") (pintype "bidirectional"))
    )
    (net (code "57") (name "Net-(U$3-OUT14)") (class "Default")
      (node (ref "U$3") (pin "8") (pinfunction "OUT14_8") (pintype "output"))
      (node (ref "U$4") (pin "18") (pinfunction "18_18") (pintype "bidirectional"))
    )
    (net (code "58") (name "Net-(U$3-OUT15)") (class "Default")
      (node (ref "U$3") (pin "7") (pinfunction "OUT15_7") (pintype "output"))
      (node (ref "U$4") (pin "19") (pinfunction "19_19") (pintype "bidirectional"))
    )
    (net (code "59") (name "Net-(U$3-OUT16)") (class "Default")
      (node (ref "U$3") (pin "6") (pinfunction "OUT16_6") (pintype "output"))
      (node (ref "U$4") (pin "20") (pinfunction "20_20") (pintype "bidirectional"))
    )
    (net (code "60") (name "Net-(U$3-OUT17)") (class "Default")
      (node (ref "U$3") (pin "5") (pinfunction "OUT17_5") (pintype "output"))
      (node (ref "U$4") (pin "21") (pinfunction "21_21") (pintype "bidirectional"))
    )
    (net (code "61") (name "Net-(U$4-11FIL-)") (class "Default")
      (node (ref "U$4") (pin "11") (pinfunction "11FIL-_11") (pintype "bidirectional"))
      (node (ref "U$6") (pin "1") (pinfunction "1FIL+_1") (pintype "bidirectional"))
    )
    (net (code "62") (name "Net-(U$5-DIN)") (class "Default")
      (node (ref "U$5") (pin "27") (pinfunction "DIN_27") (pintype "input"))
      (node (ref "U$7") (pin "2") (pinfunction "DOUT_2") (pintype "output"))
    )
    (net (code "63") (name "Net-(U$5-OUT0)") (class "Default")
      (node (ref "U$5") (pin "26") (pinfunction "OUT0_26") (pintype "output"))
      (node (ref "U$6") (pin "2") (pinfunction "2_2") (pintype "bidirectional"))
    )
    (net (code "64") (name "Net-(U$5-OUT1)") (class "Default")
      (node (ref "U$5") (pin "25") (pinfunction "OUT1_25") (pintype "output"))
      (node (ref "U$6") (pin "3") (pinfunction "3_3") (pintype "bidirectional"))
    )
    (net (code "65") (name "Net-(U$5-OUT2)") (class "Default")
      (node (ref "U$5") (pin "24") (pinfunction "OUT2_24") (pintype "output"))
      (node (ref "U$6") (pin "4") (pinfunction "4_4") (pintype "bidirectional"))
    )
    (net (code "66") (name "Net-(U$5-OUT3)") (class "Default")
      (node (ref "U$5") (pin "23") (pinfunction "OUT3_23") (pintype "output"))
      (node (ref "U$6") (pin "5") (pinfunction "5_5") (pintype "bidirectional"))
    )
    (net (code "67") (name "Net-(U$5-OUT4)") (class "Default")
      (node (ref "U$5") (pin "22") (pinfunction "OUT4_22") (pintype "output"))
      (node (ref "U$6") (pin "6") (pinfunction "6_6") (pintype "bidirectional"))
    )
    (net (code "68") (name "Net-(U$5-OUT5)") (class "Default")
      (node (ref "U$5") (pin "21") (pinfunction "OUT5_21") (pintype "output"))
      (node (ref "U$6") (pin "7") (pinfunction "7_7") (pintype "bidirectional"))
    )
    (net (code "69") (name "Net-(U$5-OUT6)") (class "Default")
      (node (ref "U$5") (pin "20") (pinfunction "OUT6_20") (pintype "output"))
      (node (ref "U$6") (pin "8") (pinfunction "8_8") (pintype "bidirectional"))
    )
    (net (code "70") (name "Net-(U$5-OUT7)") (class "Default")
      (node (ref "U$5") (pin "19") (pinfunction "OUT7_19") (pintype "output"))
      (node (ref "U$6") (pin "9") (pinfunction "9_9") (pintype "bidirectional"))
    )
    (net (code "71") (name "Net-(U$5-OUT8)") (class "Default")
      (node (ref "U$5") (pin "18") (pinfunction "OUT8_18") (pintype "output"))
      (node (ref "U$6") (pin "10") (pinfunction "10_10") (pintype "bidirectional"))
    )
    (net (code "72") (name "Net-(U$5-OUT9)") (class "Default")
      (node (ref "U$5") (pin "17") (pinfunction "OUT9_17") (pintype "output"))
      (node (ref "U$6") (pin "13") (pinfunction "13_13") (pintype "bidirectional"))
    )
    (net (code "73") (name "Net-(U$5-OUT10)") (class "Default")
      (node (ref "U$5") (pin "12") (pinfunction "OUT10_12") (pintype "output"))
      (node (ref "U$6") (pin "14") (pinfunction "14_14") (pintype "bidirectional"))
    )
    (net (code "74") (name "Net-(U$5-OUT11)") (class "Default")
      (node (ref "U$5") (pin "11") (pinfunction "OUT11_11") (pintype "output"))
      (node (ref "U$6") (pin "15") (pinfunction "15_15") (pintype "bidirectional"))
    )
    (net (code "75") (name "Net-(U$5-OUT12)") (class "Default")
      (node (ref "U$5") (pin "10") (pinfunction "OUT12_10") (pintype "output"))
      (node (ref "U$6") (pin "16") (pinfunction "16_16") (pintype "bidirectional"))
    )
    (net (code "76") (name "Net-(U$5-OUT13)") (class "Default")
      (node (ref "U$5") (pin "9") (pinfunction "OUT13_9") (pintype "output"))
      (node (ref "U$6") (pin "17") (pinfunction "17_17") (pintype "bidirectional"))
    )
    (net (code "77") (name "Net-(U$5-OUT14)") (class "Default")
      (node (ref "U$5") (pin "8") (pinfunction "OUT14_8") (pintype "output"))
      (node (ref "U$6") (pin "18") (pinfunction "18_18") (pintype "bidirectional"))
    )
    (net (code "78") (name "Net-(U$5-OUT15)") (class "Default")
      (node (ref "U$5") (pin "7") (pinfunction "OUT15_7") (pintype "output"))
      (node (ref "U$6") (pin "19") (pinfunction "19_19") (pintype "bidirectional"))
    )
    (net (code "79") (name "Net-(U$5-OUT16)") (class "Default")
      (node (ref "U$5") (pin "6") (pinfunction "OUT16_6") (pintype "output"))
      (node (ref "U$6") (pin "20") (pinfunction "20_20") (pintype "bidirectional"))
    )
    (net (code "80") (name "Net-(U$5-OUT17)") (class "Default")
      (node (ref "U$5") (pin "5") (pinfunction "OUT17_5") (pintype "output"))
      (node (ref "U$6") (pin "21") (pinfunction "21_21") (pintype "bidirectional"))
    )
    (net (code "81") (name "Net-(U$6-11FIL-)") (class "Default")
      (node (ref "U$6") (pin "11") (pinfunction "11FIL-_11") (pintype "bidirectional"))
      (node (ref "U$8") (pin "1") (pinfunction "1FIL+_1") (pintype "bidirectional"))
    )
    (net (code "82") (name "Net-(U$7-DIN)") (class "Default")
      (node (ref "U$7") (pin "27") (pinfunction "DIN_27") (pintype "input"))
      (node (ref "U$9") (pin "2") (pinfunction "DOUT_2") (pintype "output"))
    )
    (net (code "83") (name "Net-(U$7-OUT0)") (class "Default")
      (node (ref "U$7") (pin "26") (pinfunction "OUT0_26") (pintype "output"))
      (node (ref "U$8") (pin "2") (pinfunction "2_2") (pintype "bidirectional"))
    )
    (net (code "84") (name "Net-(U$7-OUT1)") (class "Default")
      (node (ref "U$7") (pin "25") (pinfunction "OUT1_25") (pintype "output"))
      (node (ref "U$8") (pin "3") (pinfunction "3_3") (pintype "bidirectional"))
    )
    (net (code "85") (name "Net-(U$7-OUT2)") (class "Default")
      (node (ref "U$7") (pin "24") (pinfunction "OUT2_24") (pintype "output"))
      (node (ref "U$8") (pin "4") (pinfunction "4_4") (pintype "bidirectional"))
    )
    (net (code "86") (name "Net-(U$7-OUT3)") (class "Default")
      (node (ref "U$7") (pin "23") (pinfunction "OUT3_23") (pintype "output"))
      (node (ref "U$8") (pin "5") (pinfunction "5_5") (pintype "bidirectional"))
    )
    (net (code "87") (name "Net-(U$7-OUT4)") (class "Default")
      (node (ref "U$7") (pin "22") (pinfunction "OUT4_22") (pintype "output"))
      (node (ref "U$8") (pin "6") (pinfunction "6_6") (pintype "bidirectional"))
    )
    (net (code "88") (name "Net-(U$7-OUT5)") (class "Default")
      (node (ref "U$7") (pin "21") (pinfunction "OUT5_21") (pintype "output"))
      (node (ref "U$8") (pin "7") (pinfunction "7_7") (pintype "bidirectional"))
    )
    (net (code "89") (name "Net-(U$7-OUT6)") (class "Default")
      (node (ref "U$7") (pin "20") (pinfunction "OUT6_20") (pintype "output"))
      (node (ref "U$8") (pin "8") (pinfunction "8_8") (pintype "bidirectional"))
    )
    (net (code "90") (name "Net-(U$7-OUT7)") (class "Default")
      (node (ref "U$7") (pin "19") (pinfunction "OUT7_19") (pintype "output"))
      (node (ref "U$8") (pin "9") (pinfunction "9_9") (pintype "bidirectional"))
    )
    (net (code "91") (name "Net-(U$7-OUT8)") (class "Default")
      (node (ref "U$7") (pin "18") (pinfunction "OUT8_18") (pintype "output"))
      (node (ref "U$8") (pin "10") (pinfunction "10_10") (pintype "bidirectional"))
    )
    (net (code "92") (name "Net-(U$7-OUT9)") (class "Default")
      (node (ref "U$7") (pin "17") (pinfunction "OUT9_17") (pintype "output"))
      (node (ref "U$8") (pin "13") (pinfunction "13_13") (pintype "bidirectional"))
    )
    (net (code "93") (name "Net-(U$7-OUT10)") (class "Default")
      (node (ref "U$7") (pin "12") (pinfunction "OUT10_12") (pintype "output"))
      (node (ref "U$8") (pin "14") (pinfunction "14_14") (pintype "bidirectional"))
    )
    (net (code "94") (name "Net-(U$7-OUT11)") (class "Default")
      (node (ref "U$7") (pin "11") (pinfunction "OUT11_11") (pintype "output"))
      (node (ref "U$8") (pin "15") (pinfunction "15_15") (pintype "bidirectional"))
    )
    (net (code "95") (name "Net-(U$7-OUT12)") (class "Default")
      (node (ref "U$7") (pin "10") (pinfunction "OUT12_10") (pintype "output"))
      (node (ref "U$8") (pin "16") (pinfunction "16_16") (pintype "bidirectional"))
    )
    (net (code "96") (name "Net-(U$7-OUT13)") (class "Default")
      (node (ref "U$7") (pin "9") (pinfunction "OUT13_9") (pintype "output"))
      (node (ref "U$8") (pin "17") (pinfunction "17_17") (pintype "bidirectional"))
    )
    (net (code "97") (name "Net-(U$7-OUT14)") (class "Default")
      (node (ref "U$7") (pin "8") (pinfunction "OUT14_8") (pintype "output"))
      (node (ref "U$8") (pin "18") (pinfunction "18_18") (pintype "bidirectional"))
    )
    (net (code "98") (name "Net-(U$7-OUT15)") (class "Default")
      (node (ref "U$7") (pin "7") (pinfunction "OUT15_7") (pintype "output"))
      (node (ref "U$8") (pin "19") (pinfunction "19_19") (pintype "bidirectional"))
    )
    (net (code "99") (name "Net-(U$7-OUT16)") (class "Default")
      (node (ref "U$7") (pin "6") (pinfunction "OUT16_6") (pintype "output"))
      (node (ref "U$8") (pin "20") (pinfunction "20_20") (pintype "bidirectional"))
    )
    (net (code "100") (name "Net-(U$7-OUT17)") (class "Default")
      (node (ref "U$7") (pin "5") (pinfunction "OUT17_5") (pintype "output"))
      (node (ref "U$8") (pin "21") (pinfunction "21_21") (pintype "bidirectional"))
    )
    (net (code "101") (name "Net-(U$9-OUT0)") (class "Default")
      (node (ref "U$10") (pin "2") (pinfunction "2_2") (pintype "bidirectional"))
      (node (ref "U$9") (pin "26") (pinfunction "OUT0_26") (pintype "output"))
    )
    (net (code "102") (name "Net-(U$9-OUT1)") (class "Default")
      (node (ref "U$10") (pin "3") (pinfunction "3_3") (pintype "bidirectional"))
      (node (ref "U$9") (pin "25") (pinfunction "OUT1_25") (pintype "output"))
    )
    (net (code "103") (name "Net-(U$9-OUT2)") (class "Default")
      (node (ref "U$10") (pin "4") (pinfunction "4_4") (pintype "bidirectional"))
      (node (ref "U$9") (pin "24") (pinfunction "OUT2_24") (pintype "output"))
    )
    (net (code "104") (name "Net-(U$9-OUT3)") (class "Default")
      (node (ref "U$10") (pin "5") (pinfunction "5_5") (pintype "bidirectional"))
      (node (ref "U$9") (pin "23") (pinfunction "OUT3_23") (pintype "output"))
    )
    (net (code "105") (name "Net-(U$9-OUT4)") (class "Default")
      (node (ref "U$10") (pin "6") (pinfunction "6_6") (pintype "bidirectional"))
      (node (ref "U$9") (pin "22") (pinfunction "OUT4_22") (pintype "output"))
    )
    (net (code "106") (name "Net-(U$9-OUT5)") (class "Default")
      (node (ref "U$10") (pin "7") (pinfunction "7_7") (pintype "bidirectional"))
      (node (ref "U$9") (pin "21") (pinfunction "OUT5_21") (pintype "output"))
    )
    (net (code "107") (name "Net-(U$9-OUT6)") (class "Default")
      (node (ref "U$10") (pin "8") (pinfunction "8_8") (pintype "bidirectional"))
      (node (ref "U$9") (pin "20") (pinfunction "OUT6_20") (pintype "output"))
    )
    (net (code "108") (name "Net-(U$9-OUT7)") (class "Default")
      (node (ref "U$10") (pin "9") (pinfunction "9_9") (pintype "bidirectional"))
      (node (ref "U$9") (pin "19") (pinfunction "OUT7_19") (pintype "output"))
    )
    (net (code "109") (name "Net-(U$9-OUT8)") (class "Default")
      (node (ref "U$10") (pin "10") (pinfunction "10_10") (pintype "bidirectional"))
      (node (ref "U$9") (pin "18") (pinfunction "OUT8_18") (pintype "output"))
    )
    (net (code "110") (name "Net-(U$9-OUT9)") (class "Default")
      (node (ref "U$10") (pin "13") (pinfunction "13_13") (pintype "bidirectional"))
      (node (ref "U$9") (pin "17") (pinfunction "OUT9_17") (pintype "output"))
    )
    (net (code "111") (name "Net-(U$9-OUT10)") (class "Default")
      (node (ref "U$10") (pin "14") (pinfunction "14_14") (pintype "bidirectional"))
      (node (ref "U$9") (pin "12") (pinfunction "OUT10_12") (pintype "output"))
    )
    (net (code "112") (name "Net-(U$9-OUT11)") (class "Default")
      (node (ref "U$10") (pin "15") (pinfunction "15_15") (pintype "bidirectional"))
      (node (ref "U$9") (pin "11") (pinfunction "OUT11_11") (pintype "output"))
    )
    (net (code "113") (name "Net-(U$9-OUT12)") (class "Default")
      (node (ref "U$10") (pin "16") (pinfunction "16_16") (pintype "bidirectional"))
      (node (ref "U$9") (pin "10") (pinfunction "OUT12_10") (pintype "output"))
    )
    (net (code "114") (name "Net-(U$9-OUT13)") (class "Default")
      (node (ref "U$10") (pin "17") (pinfunction "17_17") (pintype "bidirectional"))
      (node (ref "U$9") (pin "9") (pinfunction "OUT13_9") (pintype "output"))
    )
    (net (code "115") (name "Net-(U$9-OUT14)") (class "Default")
      (node (ref "U$10") (pin "18") (pinfunction "18_18") (pintype "bidirectional"))
      (node (ref "U$9") (pin "8") (pinfunction "OUT14_8") (pintype "output"))
    )
    (net (code "116") (name "Net-(U$9-OUT15)") (class "Default")
      (node (ref "U$10") (pin "19") (pinfunction "19_19") (pintype "bidirectional"))
      (node (ref "U$9") (pin "7") (pinfunction "OUT15_7") (pintype "output"))
    )
    (net (code "117") (name "Net-(U$9-OUT16)") (class "Default")
      (node (ref "U$10") (pin "20") (pinfunction "20_20") (pintype "bidirectional"))
      (node (ref "U$9") (pin "6") (pinfunction "OUT16_6") (pintype "output"))
    )
    (net (code "118") (name "Net-(U$9-OUT17)") (class "Default")
      (node (ref "U$10") (pin "21") (pinfunction "21_21") (pintype "bidirectional"))
      (node (ref "U$9") (pin "5") (pinfunction "OUT17_5") (pintype "output"))
    )
    (net (code "119") (name "Net-(U$10-1FIL+)") (class "Default")
      (node (ref "U$10") (pin "1") (pinfunction "1FIL+_1") (pintype "bidirectional"))
      (node (ref "U$8") (pin "11") (pinfunction "11FIL-_11") (pintype "bidirectional"))
    )
    (net (code "120") (name "Net-(U$11-DIN)") (class "Default")
      (node (ref "U$11") (pin "27") (pinfunction "DIN_27") (pintype "input"))
      (node (ref "U$13") (pin "2") (pinfunction "DOUT_2") (pintype "output"))
    )
    (net (code "121") (name "Net-(U$11-DOUT)") (class "Default")
      (node (ref "U$11") (pin "2") (pinfunction "DOUT_2") (pintype "output"))
      (node (ref "U$9") (pin "27") (pinfunction "DIN_27") (pintype "input"))
    )
    (net (code "122") (name "Net-(U$11-OUT0)") (class "Default")
      (node (ref "U$11") (pin "26") (pinfunction "OUT0_26") (pintype "output"))
      (node (ref "U$12") (pin "2") (pinfunction "2_2") (pintype "bidirectional"))
    )
    (net (code "123") (name "Net-(U$11-OUT1)") (class "Default")
      (node (ref "U$11") (pin "25") (pinfunction "OUT1_25") (pintype "output"))
      (node (ref "U$12") (pin "3") (pinfunction "3_3") (pintype "bidirectional"))
    )
    (net (code "124") (name "Net-(U$11-OUT2)") (class "Default")
      (node (ref "U$11") (pin "24") (pinfunction "OUT2_24") (pintype "output"))
      (node (ref "U$12") (pin "4") (pinfunction "4_4") (pintype "bidirectional"))
    )
    (net (code "125") (name "Net-(U$11-OUT3)") (class "Default")
      (node (ref "U$11") (pin "23") (pinfunction "OUT3_23") (pintype "output"))
      (node (ref "U$12") (pin "5") (pinfunction "5_5") (pintype "bidirectional"))
    )
    (net (code "126") (name "Net-(U$11-OUT4)") (class "Default")
      (node (ref "U$11") (pin "22") (pinfunction "OUT4_22") (pintype "output"))
      (node (ref "U$12") (pin "6") (pinfunction "6_6") (pintype "bidirectional"))
    )
    (net (code "127") (name "Net-(U$11-OUT5)") (class "Default")
      (node (ref "U$11") (pin "21") (pinfunction "OUT5_21") (pintype "output"))
      (node (ref "U$12") (pin "7") (pinfunction "7_7") (pintype "bidirectional"))
    )
    (net (code "128") (name "Net-(U$11-OUT6)") (class "Default")
      (node (ref "U$11") (pin "20") (pinfunction "OUT6_20") (pintype "output"))
      (node (ref "U$12") (pin "8") (pinfunction "8_8") (pintype "bidirectional"))
    )
    (net (code "129") (name "Net-(U$11-OUT7)") (class "Default")
      (node (ref "U$11") (pin "19") (pinfunction "OUT7_19") (pintype "output"))
      (node (ref "U$12") (pin "9") (pinfunction "9_9") (pintype "bidirectional"))
    )
    (net (code "130") (name "Net-(U$11-OUT8)") (class "Default")
      (node (ref "U$11") (pin "18") (pinfunction "OUT8_18") (pintype "output"))
      (node (ref "U$12") (pin "10") (pinfunction "10_10") (pintype "bidirectional"))
    )
    (net (code "131") (name "Net-(U$11-OUT9)") (class "Default")
      (node (ref "U$11") (pin "17") (pinfunction "OUT9_17") (pintype "output"))
      (node (ref "U$12") (pin "13") (pinfunction "13_13") (pintype "bidirectional"))
    )
    (net (code "132") (name "Net-(U$11-OUT10)") (class "Default")
      (node (ref "U$11") (pin "12") (pinfunction "OUT10_12") (pintype "output"))
      (node (ref "U$12") (pin "14") (pinfunction "14_14") (pintype "bidirectional"))
    )
    (net (code "133") (name "Net-(U$11-OUT11)") (class "Default")
      (node (ref "U$11") (pin "11") (pinfunction "OUT11_11") (pintype "output"))
      (node (ref "U$12") (pin "15") (pinfunction "15_15") (pintype "bidirectional"))
    )
    (net (code "134") (name "Net-(U$11-OUT12)") (class "Default")
      (node (ref "U$11") (pin "10") (pinfunction "OUT12_10") (pintype "output"))
      (node (ref "U$12") (pin "16") (pinfunction "16_16") (pintype "bidirectional"))
    )
    (net (code "135") (name "Net-(U$11-OUT13)") (class "Default")
      (node (ref "U$11") (pin "9") (pinfunction "OUT13_9") (pintype "output"))
      (node (ref "U$12") (pin "17") (pinfunction "17_17") (pintype "bidirectional"))
    )
    (net (code "136") (name "Net-(U$11-OUT14)") (class "Default")
      (node (ref "U$11") (pin "8") (pinfunction "OUT14_8") (pintype "output"))
      (node (ref "U$12") (pin "18") (pinfunction "18_18") (pintype "bidirectional"))
    )
    (net (code "137") (name "Net-(U$11-OUT15)") (class "Default")
      (node (ref "U$11") (pin "7") (pinfunction "OUT15_7") (pintype "output"))
      (node (ref "U$12") (pin "19") (pinfunction "19_19") (pintype "bidirectional"))
    )
    (net (code "138") (name "Net-(U$11-OUT16)") (class "Default")
      (node (ref "U$11") (pin "6") (pinfunction "OUT16_6") (pintype "output"))
      (node (ref "U$12") (pin "20") (pinfunction "20_20") (pintype "bidirectional"))
    )
    (net (code "139") (name "Net-(U$11-OUT17)") (class "Default")
      (node (ref "U$11") (pin "5") (pinfunction "OUT17_5") (pintype "output"))
      (node (ref "U$12") (pin "21") (pinfunction "21_21") (pintype "bidirectional"))
    )
    (net (code "140") (name "Net-(U$12-11FIL-)") (class "Default")
      (node (ref "U$12") (pin "11") (pinfunction "11FIL-_11") (pintype "bidirectional"))
      (node (ref "U$14") (pin "1") (pinfunction "1FIL+_1") (pintype "bidirectional"))
    )
    (net (code "141") (name "Net-(U$13-DIN)") (class "Default")
      (node (ref "U$13") (pin "27") (pinfunction "DIN_27") (pintype "input"))
      (node (ref "U$15") (pin "2") (pinfunction "DOUT_2") (pintype "output"))
    )
    (net (code "142") (name "Net-(U$13-OUT0)") (class "Default")
      (node (ref "U$13") (pin "26") (pinfunction "OUT0_26") (pintype "output"))
      (node (ref "U$14") (pin "2") (pinfunction "2_2") (pintype "bidirectional"))
    )
    (net (code "143") (name "Net-(U$13-OUT1)") (class "Default")
      (node (ref "U$13") (pin "25") (pinfunction "OUT1_25") (pintype "output"))
      (node (ref "U$14") (pin "3") (pinfunction "3_3") (pintype "bidirectional"))
    )
    (net (code "144") (name "Net-(U$13-OUT2)") (class "Default")
      (node (ref "U$13") (pin "24") (pinfunction "OUT2_24") (pintype "output"))
      (node (ref "U$14") (pin "4") (pinfunction "4_4") (pintype "bidirectional"))
    )
    (net (code "145") (name "Net-(U$13-OUT3)") (class "Default")
      (node (ref "U$13") (pin "23") (pinfunction "OUT3_23") (pintype "output"))
      (node (ref "U$14") (pin "5") (pinfunction "5_5") (pintype "bidirectional"))
    )
    (net (code "146") (name "Net-(U$13-OUT4)") (class "Default")
      (node (ref "U$13") (pin "22") (pinfunction "OUT4_22") (pintype "output"))
      (node (ref "U$14") (pin "6") (pinfunction "6_6") (pintype "bidirectional"))
    )
    (net (code "147") (name "Net-(U$13-OUT5)") (class "Default")
      (node (ref "U$13") (pin "21") (pinfunction "OUT5_21") (pintype "output"))
      (node (ref "U$14") (pin "7") (pinfunction "7_7") (pintype "bidirectional"))
    )
    (net (code "148") (name "Net-(U$13-OUT6)") (class "Default")
      (node (ref "U$13") (pin "20") (pinfunction "OUT6_20") (pintype "output"))
      (node (ref "U$14") (pin "8") (pinfunction "8_8") (pintype "bidirectional"))
    )
    (net (code "149") (name "Net-(U$13-OUT7)") (class "Default")
      (node (ref "U$13") (pin "19") (pinfunction "OUT7_19") (pintype "output"))
      (node (ref "U$14") (pin "9") (pinfunction "9_9") (pintype "bidirectional"))
    )
    (net (code "150") (name "Net-(U$13-OUT8)") (class "Default")
      (node (ref "U$13") (pin "18") (pinfunction "OUT8_18") (pintype "output"))
      (node (ref "U$14") (pin "10") (pinfunction "10_10") (pintype "bidirectional"))
    )
    (net (code "151") (name "Net-(U$13-OUT9)") (class "Default")
      (node (ref "U$13") (pin "17") (pinfunction "OUT9_17") (pintype "output"))
      (node (ref "U$14") (pin "13") (pinfunction "13_13") (pintype "bidirectional"))
    )
    (net (code "152") (name "Net-(U$13-OUT10)") (class "Default")
      (node (ref "U$13") (pin "12") (pinfunction "OUT10_12") (pintype "output"))
      (node (ref "U$14") (pin "14") (pinfunction "14_14") (pintype "bidirectional"))
    )
    (net (code "153") (name "Net-(U$13-OUT11)") (class "Default")
      (node (ref "U$13") (pin "11") (pinfunction "OUT11_11") (pintype "output"))
      (node (ref "U$14") (pin "15") (pinfunction "15_15") (pintype "bidirectional"))
    )
    (net (code "154") (name "Net-(U$13-OUT12)") (class "Default")
      (node (ref "U$13") (pin "10") (pinfunction "OUT12_10") (pintype "output"))
      (node (ref "U$14") (pin "16") (pinfunction "16_16") (pintype "bidirectional"))
    )
    (net (code "155") (name "Net-(U$13-OUT13)") (class "Default")
      (node (ref "U$13") (pin "9") (pinfunction "OUT13_9") (pintype "output"))
      (node (ref "U$14") (pin "17") (pinfunction "17_17") (pintype "bidirectional"))
    )
    (net (code "156") (name "Net-(U$13-OUT14)") (class "Default")
      (node (ref "U$13") (pin "8") (pinfunction "OUT14_8") (pintype "output"))
      (node (ref "U$14") (pin "18") (pinfunction "18_18") (pintype "bidirectional"))
    )
    (net (code "157") (name "Net-(U$13-OUT15)") (class "Default")
      (node (ref "U$13") (pin "7") (pinfunction "OUT15_7") (pintype "output"))
      (node (ref "U$14") (pin "19") (pinfunction "19_19") (pintype "bidirectional"))
    )
    (net (code "158") (name "Net-(U$13-OUT16)") (class "Default")
      (node (ref "U$13") (pin "6") (pinfunction "OUT16_6") (pintype "output"))
      (node (ref "U$14") (pin "20") (pinfunction "20_20") (pintype "bidirectional"))
    )
    (net (code "159") (name "Net-(U$13-OUT17)") (class "Default")
      (node (ref "U$13") (pin "5") (pinfunction "OUT17_5") (pintype "output"))
      (node (ref "U$14") (pin "21") (pinfunction "21_21") (pintype "bidirectional"))
    )
    (net (code "160") (name "Net-(U$14-11FIL-)") (class "Default")
      (node (ref "U$14") (pin "11") (pinfunction "11FIL-_11") (pintype "bidirectional"))
      (node (ref "U$16") (pin "1") (pinfunction "1FIL+_1") (pintype "bidirectional"))
    )
    (net (code "161") (name "Net-(U$15-DIN)") (class "Default")
      (node (ref "U$15") (pin "27") (pinfunction "DIN_27") (pintype "input"))
      (node (ref "U$17") (pin "2") (pinfunction "DOUT_2") (pintype "output"))
    )
    (net (code "162") (name "Net-(U$15-OUT0)") (class "Default")
      (node (ref "U$15") (pin "26") (pinfunction "OUT0_26") (pintype "output"))
      (node (ref "U$16") (pin "2") (pinfunction "2_2") (pintype "bidirectional"))
    )
    (net (code "163") (name "Net-(U$15-OUT1)") (class "Default")
      (node (ref "U$15") (pin "25") (pinfunction "OUT1_25") (pintype "output"))
      (node (ref "U$16") (pin "3") (pinfunction "3_3") (pintype "bidirectional"))
    )
    (net (code "164") (name "Net-(U$15-OUT2)") (class "Default")
      (node (ref "U$15") (pin "24") (pinfunction "OUT2_24") (pintype "output"))
      (node (ref "U$16") (pin "4") (pinfunction "4_4") (pintype "bidirectional"))
    )
    (net (code "165") (name "Net-(U$15-OUT3)") (class "Default")
      (node (ref "U$15") (pin "23") (pinfunction "OUT3_23") (pintype "output"))
      (node (ref "U$16") (pin "5") (pinfunction "5_5") (pintype "bidirectional"))
    )
    (net (code "166") (name "Net-(U$15-OUT4)") (class "Default")
      (node (ref "U$15") (pin "22") (pinfunction "OUT4_22") (pintype "output"))
      (node (ref "U$16") (pin "6") (pinfunction "6_6") (pintype "bidirectional"))
    )
    (net (code "167") (name "Net-(U$15-OUT5)") (class "Default")
      (node (ref "U$15") (pin "21") (pinfunction "OUT5_21") (pintype "output"))
      (node (ref "U$16") (pin "7") (pinfunction "7_7") (pintype "bidirectional"))
    )
    (net (code "168") (name "Net-(U$15-OUT6)") (class "Default")
      (node (ref "U$15") (pin "20") (pinfunction "OUT6_20") (pintype "output"))
      (node (ref "U$16") (pin "8") (pinfunction "8_8") (pintype "bidirectional"))
    )
    (net (code "169") (name "Net-(U$15-OUT7)") (class "Default")
      (node (ref "U$15") (pin "19") (pinfunction "OUT7_19") (pintype "output"))
      (node (ref "U$16") (pin "9") (pinfunction "9_9") (pintype "bidirectional"))
    )
    (net (code "170") (name "Net-(U$15-OUT8)") (class "Default")
      (node (ref "U$15") (pin "18") (pinfunction "OUT8_18") (pintype "output"))
      (node (ref "U$16") (pin "10") (pinfunction "10_10") (pintype "bidirectional"))
    )
    (net (code "171") (name "Net-(U$15-OUT9)") (class "Default")
      (node (ref "U$15") (pin "17") (pinfunction "OUT9_17") (pintype "output"))
      (node (ref "U$16") (pin "13") (pinfunction "13_13") (pintype "bidirectional"))
    )
    (net (code "172") (name "Net-(U$15-OUT10)") (class "Default")
      (node (ref "U$15") (pin "12") (pinfunction "OUT10_12") (pintype "output"))
      (node (ref "U$16") (pin "14") (pinfunction "14_14") (pintype "bidirectional"))
    )
    (net (code "173") (name "Net-(U$15-OUT11)") (class "Default")
      (node (ref "U$15") (pin "11") (pinfunction "OUT11_11") (pintype "output"))
      (node (ref "U$16") (pin "15") (pinfunction "15_15") (pintype "bidirectional"))
    )
    (net (code "174") (name "Net-(U$15-OUT12)") (class "Default")
      (node (ref "U$15") (pin "10") (pinfunction "OUT12_10") (pintype "output"))
      (node (ref "U$16") (pin "16") (pinfunction "16_16") (pintype "bidirectional"))
    )
    (net (code "175") (name "Net-(U$15-OUT13)") (class "Default")
      (node (ref "U$15") (pin "9") (pinfunction "OUT13_9") (pintype "output"))
      (node (ref "U$16") (pin "17") (pinfunction "17_17") (pintype "bidirectional"))
    )
    (net (code "176") (name "Net-(U$15-OUT14)") (class "Default")
      (node (ref "U$15") (pin "8") (pinfunction "OUT14_8") (pintype "output"))
      (node (ref "U$16") (pin "18") (pinfunction "18_18") (pintype "bidirectional"))
    )
    (net (code "177") (name "Net-(U$15-OUT15)") (class "Default")
      (node (ref "U$15") (pin "7") (pinfunction "OUT15_7") (pintype "output"))
      (node (ref "U$16") (pin "19") (pinfunction "19_19") (pintype "bidirectional"))
    )
    (net (code "178") (name "Net-(U$15-OUT16)") (class "Default")
      (node (ref "U$15") (pin "6") (pinfunction "OUT16_6") (pintype "output"))
      (node (ref "U$16") (pin "20") (pinfunction "20_20") (pintype "bidirectional"))
    )
    (net (code "179") (name "Net-(U$15-OUT17)") (class "Default")
      (node (ref "U$15") (pin "5") (pinfunction "OUT17_5") (pintype "output"))
      (node (ref "U$16") (pin "21") (pinfunction "21_21") (pintype "bidirectional"))
    )
    (net (code "180") (name "Net-(U$16-11FIL-)") (class "Default")
      (node (ref "U$16") (pin "11") (pinfunction "11FIL-_11") (pintype "bidirectional"))
      (node (ref "U$18") (pin "1") (pinfunction "1FIL+_1") (pintype "bidirectional"))
    )
    (net (code "181") (name "Net-(U$17-DIN)") (class "Default")
      (node (ref "U$17") (pin "27") (pinfunction "DIN_27") (pintype "input"))
      (node (ref "U$19") (pin "2") (pinfunction "DOUT_2") (pintype "output"))
    )
    (net (code "182") (name "Net-(U$17-OUT0)") (class "Default")
      (node (ref "U$17") (pin "26") (pinfunction "OUT0_26") (pintype "output"))
      (node (ref "U$18") (pin "2") (pinfunction "2_2") (pintype "bidirectional"))
    )
    (net (code "183") (name "Net-(U$17-OUT1)") (class "Default")
      (node (ref "U$17") (pin "25") (pinfunction "OUT1_25") (pintype "output"))
      (node (ref "U$18") (pin "3") (pinfunction "3_3") (pintype "bidirectional"))
    )
    (net (code "184") (name "Net-(U$17-OUT2)") (class "Default")
      (node (ref "U$17") (pin "24") (pinfunction "OUT2_24") (pintype "output"))
      (node (ref "U$18") (pin "4") (pinfunction "4_4") (pintype "bidirectional"))
    )
    (net (code "185") (name "Net-(U$17-OUT3)") (class "Default")
      (node (ref "U$17") (pin "23") (pinfunction "OUT3_23") (pintype "output"))
      (node (ref "U$18") (pin "5") (pinfunction "5_5") (pintype "bidirectional"))
    )
    (net (code "186") (name "Net-(U$17-OUT4)") (class "Default")
      (node (ref "U$17") (pin "22") (pinfunction "OUT4_22") (pintype "output"))
      (node (ref "U$18") (pin "6") (pinfunction "6_6") (pintype "bidirectional"))
    )
    (net (code "187") (name "Net-(U$17-OUT5)") (class "Default")
      (node (ref "U$17") (pin "21") (pinfunction "OUT5_21") (pintype "output"))
      (node (ref "U$18") (pin "7") (pinfunction "7_7") (pintype "bidirectional"))
    )
    (net (code "188") (name "Net-(U$17-OUT6)") (class "Default")
      (node (ref "U$17") (pin "20") (pinfunction "OUT6_20") (pintype "output"))
      (node (ref "U$18") (pin "8") (pinfunction "8_8") (pintype "bidirectional"))
    )
    (net (code "189") (name "Net-(U$17-OUT7)") (class "Default")
      (node (ref "U$17") (pin "19") (pinfunction "OUT7_19") (pintype "output"))
      (node (ref "U$18") (pin "9") (pinfunction "9_9") (pintype "bidirectional"))
    )
    (net (code "190") (name "Net-(U$17-OUT8)") (class "Default")
      (node (ref "U$17") (pin "18") (pinfunction "OUT8_18") (pintype "output"))
      (node (ref "U$18") (pin "10") (pinfunction "10_10") (pintype "bidirectional"))
    )
    (net (code "191") (name "Net-(U$17-OUT9)") (class "Default")
      (node (ref "U$17") (pin "17") (pinfunction "OUT9_17") (pintype "output"))
      (node (ref "U$18") (pin "13") (pinfunction "13_13") (pintype "bidirectional"))
    )
    (net (code "192") (name "Net-(U$17-OUT10)") (class "Default")
      (node (ref "U$17") (pin "12") (pinfunction "OUT10_12") (pintype "output"))
      (node (ref "U$18") (pin "14") (pinfunction "14_14") (pintype "bidirectional"))
    )
    (net (code "193") (name "Net-(U$17-OUT11)") (class "Default")
      (node (ref "U$17") (pin "11") (pinfunction "OUT11_11") (pintype "output"))
      (node (ref "U$18") (pin "15") (pinfunction "15_15") (pintype "bidirectional"))
    )
    (net (code "194") (name "Net-(U$17-OUT12)") (class "Default")
      (node (ref "U$17") (pin "10") (pinfunction "OUT12_10") (pintype "output"))
      (node (ref "U$18") (pin "16") (pinfunction "16_16") (pintype "bidirectional"))
    )
    (net (code "195") (name "Net-(U$17-OUT13)") (class "Default")
      (node (ref "U$17") (pin "9") (pinfunction "OUT13_9") (pintype "output"))
      (node (ref "U$18") (pin "17") (pinfunction "17_17") (pintype "bidirectional"))
    )
    (net (code "196") (name "Net-(U$17-OUT14)") (class "Default")
      (node (ref "U$17") (pin "8") (pinfunction "OUT14_8") (pintype "output"))
      (node (ref "U$18") (pin "18") (pinfunction "18_18") (pintype "bidirectional"))
    )
    (net (code "197") (name "Net-(U$17-OUT15)") (class "Default")
      (node (ref "U$17") (pin "7") (pinfunction "OUT15_7") (pintype "output"))
      (node (ref "U$18") (pin "19") (pinfunction "19_19") (pintype "bidirectional"))
    )
    (net (code "198") (name "Net-(U$17-OUT16)") (class "Default")
      (node (ref "U$17") (pin "6") (pinfunction "OUT16_6") (pintype "output"))
      (node (ref "U$18") (pin "20") (pinfunction "20_20") (pintype "bidirectional"))
    )
    (net (code "199") (name "Net-(U$17-OUT17)") (class "Default")
      (node (ref "U$17") (pin "5") (pinfunction "OUT17_5") (pintype "output"))
      (node (ref "U$18") (pin "21") (pinfunction "21_21") (pintype "bidirectional"))
    )
    (net (code "200") (name "Net-(U$18-11FIL-)") (class "Default")
      (node (ref "U$18") (pin "11") (pinfunction "11FIL-_11") (pintype "bidirectional"))
      (node (ref "U$20") (pin "1") (pinfunction "1FIL+_1") (pintype "bidirectional"))
    )
    (net (code "201") (name "Net-(U$19-OUT0)") (class "Default")
      (node (ref "U$19") (pin "26") (pinfunction "OUT0_26") (pintype "output"))
      (node (ref "U$20") (pin "2") (pinfunction "2_2") (pintype "bidirectional"))
    )
    (net (code "202") (name "Net-(U$19-OUT1)") (class "Default")
      (node (ref "U$19") (pin "25") (pinfunction "OUT1_25") (pintype "output"))
      (node (ref "U$20") (pin "3") (pinfunction "3_3") (pintype "bidirectional"))
    )
    (net (code "203") (name "Net-(U$19-OUT2)") (class "Default")
      (node (ref "U$19") (pin "24") (pinfunction "OUT2_24") (pintype "output"))
      (node (ref "U$20") (pin "4") (pinfunction "4_4") (pintype "bidirectional"))
    )
    (net (code "204") (name "Net-(U$19-OUT3)") (class "Default")
      (node (ref "U$19") (pin "23") (pinfunction "OUT3_23") (pintype "output"))
      (node (ref "U$20") (pin "5") (pinfunction "5_5") (pintype "bidirectional"))
    )
    (net (code "205") (name "Net-(U$19-OUT4)") (class "Default")
      (node (ref "U$19") (pin "22") (pinfunction "OUT4_22") (pintype "output"))
      (node (ref "U$20") (pin "6") (pinfunction "6_6") (pintype "bidirectional"))
    )
    (net (code "206") (name "Net-(U$19-OUT5)") (class "Default")
      (node (ref "U$19") (pin "21") (pinfunction "OUT5_21") (pintype "output"))
      (node (ref "U$20") (pin "7") (pinfunction "7_7") (pintype "bidirectional"))
    )
    (net (code "207") (name "Net-(U$19-OUT6)") (class "Default")
      (node (ref "U$19") (pin "20") (pinfunction "OUT6_20") (pintype "output"))
      (node (ref "U$20") (pin "8") (pinfunction "8_8") (pintype "bidirectional"))
    )
    (net (code "208") (name "Net-(U$19-OUT7)") (class "Default")
      (node (ref "U$19") (pin "19") (pinfunction "OUT7_19") (pintype "output"))
      (node (ref "U$20") (pin "9") (pinfunction "9_9") (pintype "bidirectional"))
    )
    (net (code "209") (name "Net-(U$19-OUT8)") (class "Default")
      (node (ref "U$19") (pin "18") (pinfunction "OUT8_18") (pintype "output"))
      (node (ref "U$20") (pin "10") (pinfunction "10_10") (pintype "bidirectional"))
    )
    (net (code "210") (name "Net-(U$19-OUT9)") (class "Default")
      (node (ref "U$19") (pin "17") (pinfunction "OUT9_17") (pintype "output"))
      (node (ref "U$20") (pin "13") (pinfunction "13_13") (pintype "bidirectional"))
    )
    (net (code "211") (name "Net-(U$19-OUT10)") (class "Default")
      (node (ref "U$19") (pin "12") (pinfunction "OUT10_12") (pintype "output"))
      (node (ref "U$20") (pin "14") (pinfunction "14_14") (pintype "bidirectional"))
    )
    (net (code "212") (name "Net-(U$19-OUT11)") (class "Default")
      (node (ref "U$19") (pin "11") (pinfunction "OUT11_11") (pintype "output"))
      (node (ref "U$20") (pin "15") (pinfunction "15_15") (pintype "bidirectional"))
    )
    (net (code "213") (name "Net-(U$19-OUT12)") (class "Default")
      (node (ref "U$19") (pin "10") (pinfunction "OUT12_10") (pintype "output"))
      (node (ref "U$20") (pin "16") (pinfunction "16_16") (pintype "bidirectional"))
    )
    (net (code "214") (name "Net-(U$19-OUT13)") (class "Default")
      (node (ref "U$19") (pin "9") (pinfunction "OUT13_9") (pintype "output"))
      (node (ref "U$20") (pin "17") (pinfunction "17_17") (pintype "bidirectional"))
    )
    (net (code "215") (name "Net-(U$19-OUT14)") (class "Default")
      (node (ref "U$19") (pin "8") (pinfunction "OUT14_8") (pintype "output"))
      (node (ref "U$20") (pin "18") (pinfunction "18_18") (pintype "bidirectional"))
    )
    (net (code "216") (name "Net-(U$19-OUT15)") (class "Default")
      (node (ref "U$19") (pin "7") (pinfunction "OUT15_7") (pintype "output"))
      (node (ref "U$20") (pin "19") (pinfunction "19_19") (pintype "bidirectional"))
    )
    (net (code "217") (name "Net-(U$19-OUT16)") (class "Default")
      (node (ref "U$19") (pin "6") (pinfunction "OUT16_6") (pintype "output"))
      (node (ref "U$20") (pin "20") (pinfunction "20_20") (pintype "bidirectional"))
    )
    (net (code "218") (name "Net-(U$19-OUT17)") (class "Default")
      (node (ref "U$19") (pin "5") (pinfunction "OUT17_5") (pintype "output"))
      (node (ref "U$20") (pin "21") (pinfunction "21_21") (pintype "bidirectional"))
    )
    (net (code "219") (name "unconnected-(L10-DOUT-Pad2-DOUT)") (class "Default")
      (node (ref "L10") (pin "2-DOUT") (pinfunction "DOUT_2-DOUT") (pintype "output"))
    )
    (net (code "220") (name "unconnected-(SV1-Pad5)") (class "Default")
      (node (ref "SV1") (pin "5") (pinfunction "5_5") (pintype "passive"))
    )
    (net (code "221") (name "unconnected-(SV1-Pad6)") (class "Default")
      (node (ref "SV1") (pin "6") (pinfunction "6_6") (pintype "passive"))
    )
    (net (code "222") (name "unconnected-(U$1-DOUT-Pad2)") (class "Default")
      (node (ref "U$1") (pin "2") (pinfunction "DOUT_2") (pintype "output"))
    )
    (net (code "223") (name "unconnected-(U$1-OUT18-Pad4)") (class "Default")
      (node (ref "U$1") (pin "4") (pinfunction "OUT18_4") (pintype "output"))
    )
    (net (code "224") (name "unconnected-(U$1-OUT19-Pad3)") (class "Default")
      (node (ref "U$1") (pin "3") (pinfunction "OUT19_3") (pintype "output"))
    )
    (net (code "225") (name "unconnected-(U$3-OUT18-Pad4)") (class "Default")
      (node (ref "U$3") (pin "4") (pinfunction "OUT18_4") (pintype "output"))
    )
    (net (code "226") (name "unconnected-(U$3-OUT19-Pad3)") (class "Default")
      (node (ref "U$3") (pin "3") (pinfunction "OUT19_3") (pintype "output"))
    )
    (net (code "227") (name "unconnected-(U$5-OUT18-Pad4)") (class "Default")
      (node (ref "U$5") (pin "4") (pinfunction "OUT18_4") (pintype "output"))
    )
    (net (code "228") (name "unconnected-(U$5-OUT19-Pad3)") (class "Default")
      (node (ref "U$5") (pin "3") (pinfunction "OUT19_3") (pintype "output"))
    )
    (net (code "229") (name "unconnected-(U$7-OUT18-Pad4)") (class "Default")
      (node (ref "U$7") (pin "4") (pinfunction "OUT18_4") (pintype "output"))
    )
    (net (code "230") (name "unconnected-(U$7-OUT19-Pad3)") (class "Default")
      (node (ref "U$7") (pin "3") (pinfunction "OUT19_3") (pintype "output"))
    )
    (net (code "231") (name "unconnected-(U$9-OUT18-Pad4)") (class "Default")
      (node (ref "U$9") (pin "4") (pinfunction "OUT18_4") (pintype "output"))
    )
    (net (code "232") (name "unconnected-(U$9-OUT19-Pad3)") (class "Default")
      (node (ref "U$9") (pin "3") (pinfunction "OUT19_3") (pintype "output"))
    )
    (net (code "233") (name "unconnected-(U$11-OUT18-Pad4)") (class "Default")
      (node (ref "U$11") (pin "4") (pinfunction "OUT18_4") (pintype "output"))
    )
    (net (code "234") (name "unconnected-(U$11-OUT19-Pad3)") (class "Default")
      (node (ref "U$11") (pin "3") (pinfunction "OUT19_3") (pintype "output"))
    )
    (net (code "235") (name "unconnected-(U$13-OUT18-Pad4)") (class "Default")
      (node (ref "U$13") (pin "4") (pinfunction "OUT18_4") (pintype "output"))
    )
    (net (code "236") (name "unconnected-(U$13-OUT19-Pad3)") (class "Default")
      (node (ref "U$13") (pin "3") (pinfunction "OUT19_3") (pintype "output"))
    )
    (net (code "237") (name "unconnected-(U$15-OUT18-Pad4)") (class "Default")
      (node (ref "U$15") (pin "4") (pinfunction "OUT18_4") (pintype "output"))
    )
    (net (code "238") (name "unconnected-(U$15-OUT19-Pad3)") (class "Default")
      (node (ref "U$15") (pin "3") (pinfunction "OUT19_3") (pintype "output"))
    )
    (net (code "239") (name "unconnected-(U$17-OUT18-Pad4)") (class "Default")
      (node (ref "U$17") (pin "4") (pinfunction "OUT18_4") (pintype "output"))
    )
    (net (code "240") (name "unconnected-(U$17-OUT19-Pad3)") (class "Default")
      (node (ref "U$17") (pin "3") (pinfunction "OUT19_3") (pintype "output"))
    )
    (net (code "241") (name "unconnected-(U$19-OUT18-Pad4)") (class "Default")
      (node (ref "U$19") (pin "4") (pinfunction "OUT18_4") (pintype "output"))
    )
    (net (code "242") (name "unconnected-(U$19-OUT19-Pad3)") (class "Default")
      (node (ref "U$19") (pin "3") (pinfunction "OUT19_3") (pintype "output"))
    )
  )
)
